# 2i.net
KiCad netlist of a schematic drawn in EAGLE
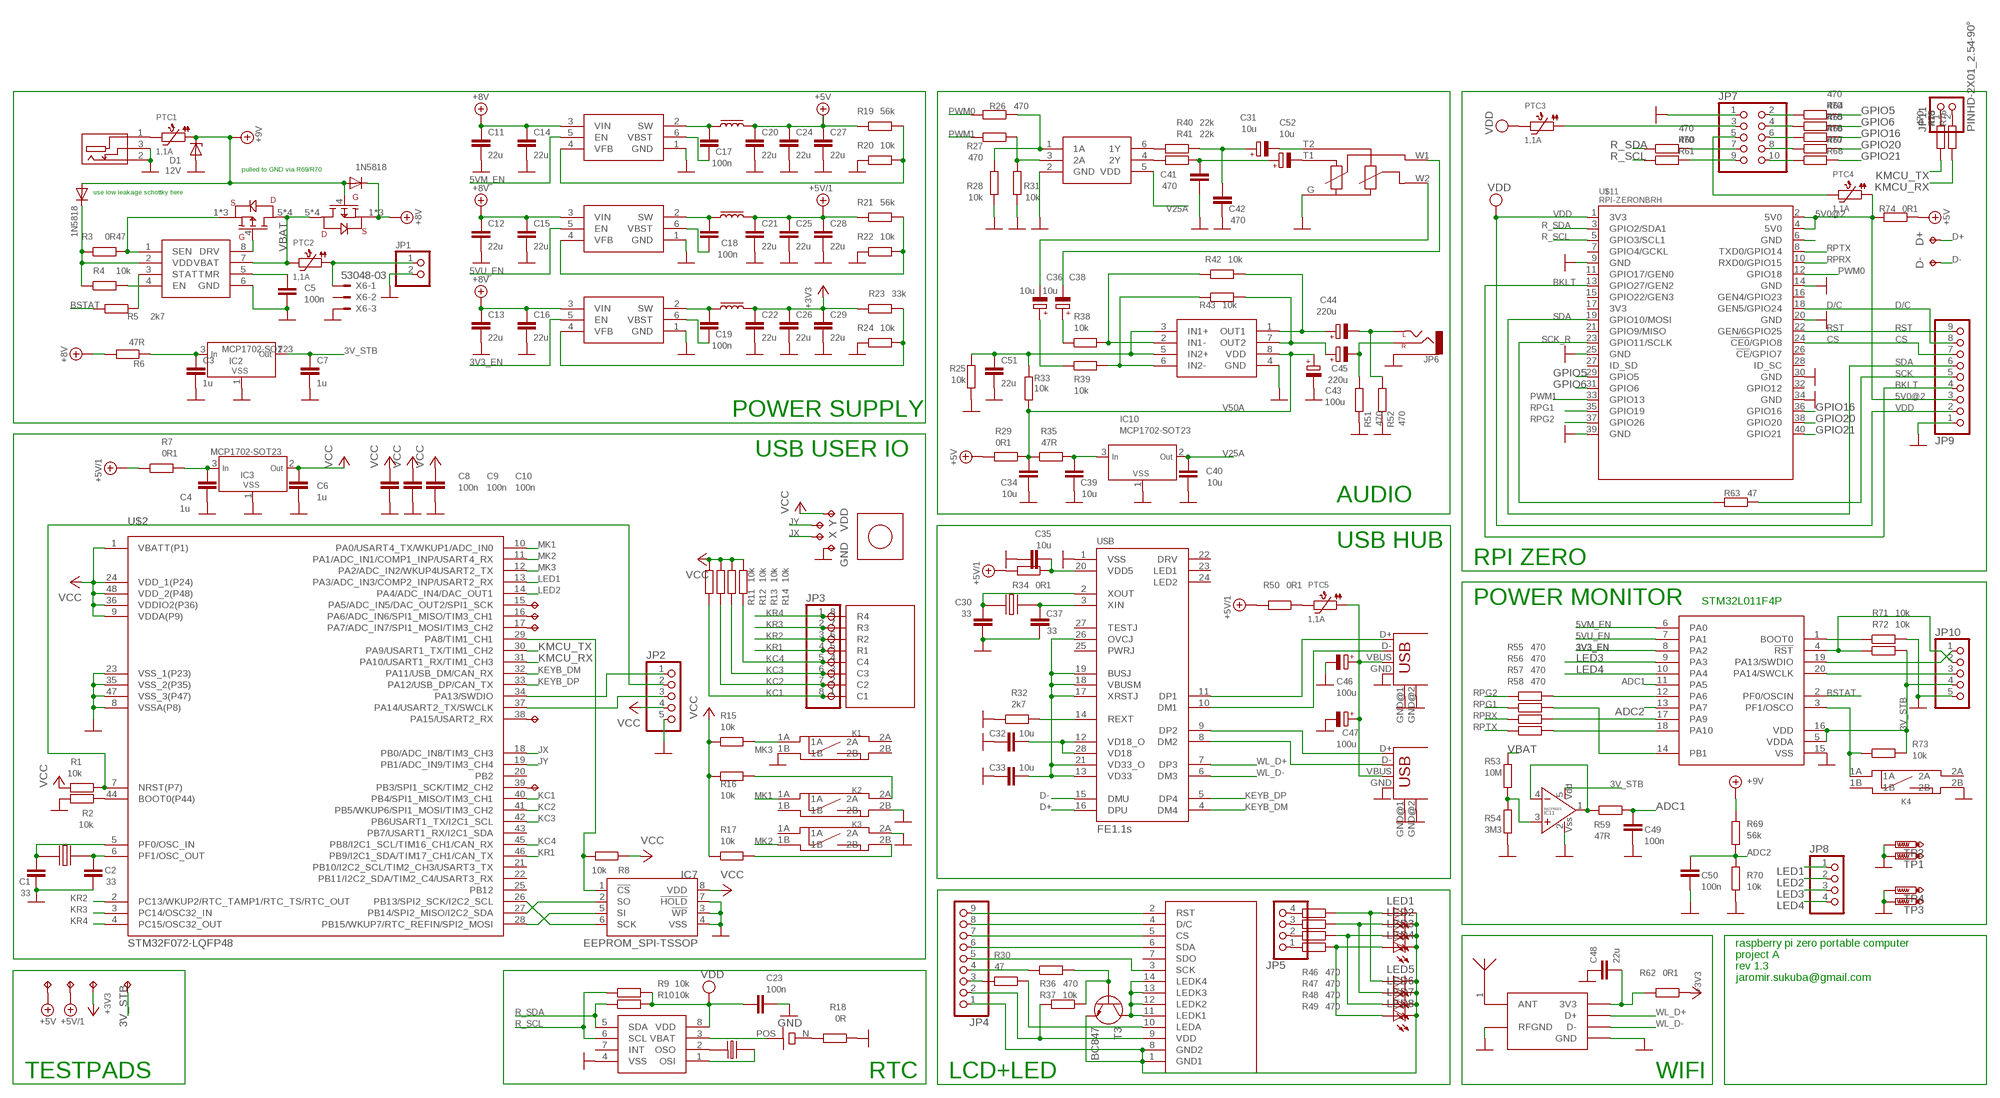
[diagram p0: schematic, sheet 1]

(export (version "E")
  (design (tool "Eeschema 10.0.6"))
  (components
    (comp (ref "ANT1")
      (value "ANT_RAINSUN_24GHZ")
      (footprint "eagle-import:ANT_RAINSUN-24G")
      (libsource (lib "eagle-import") (part "ANT_RAINSUN_24GHZ"))
    )
    (comp (ref "C1")
      (value "33")
      (footprint "eagle-import:R0805")
      (libsource (lib "eagle-import") (part "C_0806"))
    )
    (comp (ref "C2")
      (value "33")
      (footprint "eagle-import:R0805")
      (libsource (lib "eagle-import") (part "C_0806"))
    )
    (comp (ref "C3")
      (value "1u")
      (footprint "eagle-import:R0805")
      (libsource (lib "eagle-import") (part "C_0806"))
    )
    (comp (ref "C4")
      (value "1u")
      (footprint "eagle-import:R0805")
      (libsource (lib "eagle-import") (part "C_0806"))
    )
    (comp (ref "C5")
      (value "100n")
      (footprint "eagle-import:R0805")
      (libsource (lib "eagle-import") (part "C_0806"))
    )
    (comp (ref "C6")
      (value "1u")
      (footprint "eagle-import:R0805")
      (libsource (lib "eagle-import") (part "C_0806"))
    )
    (comp (ref "C7")
      (value "1u")
      (footprint "eagle-import:R0805")
      (libsource (lib "eagle-import") (part "C_0806"))
    )
    (comp (ref "C8")
      (value "100n")
      (footprint "eagle-import:R0805")
      (libsource (lib "eagle-import") (part "C_0806"))
    )
    (comp (ref "C9")
      (value "100n")
      (footprint "eagle-import:R0805")
      (libsource (lib "eagle-import") (part "C_0806"))
    )
    (comp (ref "C10")
      (value "100n")
      (footprint "eagle-import:R0805")
      (libsource (lib "eagle-import") (part "C_0806"))
    )
    (comp (ref "C11")
      (value "22u")
      (footprint "eagle-import:R0805")
      (libsource (lib "eagle-import") (part "C_0806"))
    )
    (comp (ref "C12")
      (value "22u")
      (footprint "eagle-import:R0805")
      (libsource (lib "eagle-import") (part "C_0806"))
    )
    (comp (ref "C13")
      (value "22u")
      (footprint "eagle-import:R0805")
      (libsource (lib "eagle-import") (part "C_0806"))
    )
    (comp (ref "C14")
      (value "22u")
      (footprint "eagle-import:R0805")
      (libsource (lib "eagle-import") (part "C_0806"))
    )
    (comp (ref "C15")
      (value "22u")
      (footprint "eagle-import:R0805")
      (libsource (lib "eagle-import") (part "C_0806"))
    )
    (comp (ref "C16")
      (value "22u")
      (footprint "eagle-import:R0805")
      (libsource (lib "eagle-import") (part "C_0806"))
    )
    (comp (ref "C17")
      (value "100n")
      (footprint "eagle-import:R0805")
      (libsource (lib "eagle-import") (part "C_0806"))
    )
    (comp (ref "C18")
      (value "100n")
      (footprint "eagle-import:R0805")
      (libsource (lib "eagle-import") (part "C_0806"))
    )
    (comp (ref "C19")
      (value "100n")
      (footprint "eagle-import:R0805")
      (libsource (lib "eagle-import") (part "C_0806"))
    )
    (comp (ref "C20")
      (value "22u")
      (footprint "eagle-import:R0805")
      (libsource (lib "eagle-import") (part "C_0806"))
    )
    (comp (ref "C21")
      (value "22u")
      (footprint "eagle-import:R0805")
      (libsource (lib "eagle-import") (part "C_0806"))
    )
    (comp (ref "C22")
      (value "22u")
      (footprint "eagle-import:R0805")
      (libsource (lib "eagle-import") (part "C_0806"))
    )
    (comp (ref "C23")
      (value "100n")
      (footprint "eagle-import:R0805")
      (libsource (lib "eagle-import") (part "C_0806"))
    )
    (comp (ref "C24")
      (value "22u")
      (footprint "eagle-import:R0805")
      (libsource (lib "eagle-import") (part "C_0806"))
    )
    (comp (ref "C25")
      (value "22u")
      (footprint "eagle-import:R0805")
      (libsource (lib "eagle-import") (part "C_0806"))
    )
    (comp (ref "C26")
      (value "22u")
      (footprint "eagle-import:R0805")
      (libsource (lib "eagle-import") (part "C_0806"))
    )
    (comp (ref "C27")
      (value "22u")
      (footprint "eagle-import:R0805")
      (libsource (lib "eagle-import") (part "C_0806"))
    )
    (comp (ref "C28")
      (value "22u")
      (footprint "eagle-import:R0805")
      (libsource (lib "eagle-import") (part "C_0806"))
    )
    (comp (ref "C29")
      (value "22u")
      (footprint "eagle-import:R0805")
      (libsource (lib "eagle-import") (part "C_0806"))
    )
    (comp (ref "C30")
      (value "33")
      (footprint "eagle-import:R0805")
      (libsource (lib "eagle-import") (part "C_0806"))
    )
    (comp (ref "C31")
      (value "10u")
      (footprint "eagle-import:PANASONIC_A")
      (libsource (lib "eagle-import") (part "CPOL-EUA"))
    )
    (comp (ref "C32")
      (value "10u")
      (footprint "eagle-import:R0805")
      (libsource (lib "eagle-import") (part "C_0806"))
    )
    (comp (ref "C33")
      (value "10u")
      (footprint "eagle-import:R0805")
      (libsource (lib "eagle-import") (part "C_0806"))
    )
    (comp (ref "C34")
      (value "10u")
      (footprint "eagle-import:R0805")
      (libsource (lib "eagle-import") (part "C_0806"))
    )
    (comp (ref "C35")
      (value "10u")
      (footprint "eagle-import:R0805")
      (libsource (lib "eagle-import") (part "C_0806"))
    )
    (comp (ref "C36")
      (value "10u")
      (footprint "eagle-import:PANASONIC_A")
      (libsource (lib "eagle-import") (part "CPOL-EUA"))
    )
    (comp (ref "C37")
      (value "33")
      (footprint "eagle-import:R0805")
      (libsource (lib "eagle-import") (part "C_0806"))
    )
    (comp (ref "C38")
      (value "10u")
      (footprint "eagle-import:PANASONIC_A")
      (libsource (lib "eagle-import") (part "CPOL-EUA"))
    )
    (comp (ref "C39")
      (value "10u")
      (footprint "eagle-import:R0805")
      (libsource (lib "eagle-import") (part "C_0806"))
    )
    (comp (ref "C40")
      (value "10u")
      (footprint "eagle-import:R0805")
      (libsource (lib "eagle-import") (part "C_0806"))
    )
    (comp (ref "C41")
      (value "470")
      (footprint "eagle-import:R0805")
      (libsource (lib "eagle-import") (part "C_0806"))
    )
    (comp (ref "C42")
      (value "470")
      (footprint "eagle-import:R0805")
      (libsource (lib "eagle-import") (part "C_0806"))
    )
    (comp (ref "C43")
      (value "100u")
      (footprint "eagle-import:PANASONIC_D")
      (libsource (lib "eagle-import") (part "CPOL-EUD"))
    )
    (comp (ref "C44")
      (value "220u")
      (footprint "eagle-import:PANASONIC_D")
      (libsource (lib "eagle-import") (part "CPOL-EUD"))
    )
    (comp (ref "C45")
      (value "220u")
      (footprint "eagle-import:PANASONIC_D")
      (libsource (lib "eagle-import") (part "CPOL-EUD"))
    )
    (comp (ref "C46")
      (value "100u")
      (footprint "eagle-import:PANASONIC_D")
      (libsource (lib "eagle-import") (part "CPOL-EUD"))
    )
    (comp (ref "C47")
      (value "100u")
      (footprint "eagle-import:PANASONIC_D")
      (libsource (lib "eagle-import") (part "CPOL-EUD"))
    )
    (comp (ref "C48")
      (value "22u")
      (footprint "eagle-import:R0805")
      (libsource (lib "eagle-import") (part "C_0806"))
    )
    (comp (ref "C49")
      (value "100n")
      (footprint "eagle-import:R0805")
      (libsource (lib "eagle-import") (part "C_0806"))
    )
    (comp (ref "C50")
      (value "100n")
      (footprint "eagle-import:R0805")
      (libsource (lib "eagle-import") (part "C_0806"))
    )
    (comp (ref "C51")
      (value "22u")
      (footprint "eagle-import:R0805")
      (libsource (lib "eagle-import") (part "C_0806"))
    )
    (comp (ref "C52")
      (value "10u")
      (footprint "eagle-import:PANASONIC_A")
      (libsource (lib "eagle-import") (part "CPOL-EUA"))
    )
    (comp (ref "D+")
      (value "TPTP14R")
      (footprint "eagle-import:TP14R")
      (libsource (lib "eagle-import") (part "TPTP14R"))
    )
    (comp (ref "D-")
      (value "TPTP14R")
      (footprint "eagle-import:TP14R")
      (libsource (lib "eagle-import") (part "TPTP14R"))
    )
    (comp (ref "D1")
      (value "12V")
      (footprint "eagle-import:SMB")
      (libsource (lib "eagle-import") (part "ZENER-DIODESMB"))
    )
    (comp (ref "D2")
      (value "1N5818")
      (footprint "eagle-import:SMB")
      (libsource (lib "eagle-import") (part "DIODE-SMB"))
    )
    (comp (ref "D3")
      (value "1N5818")
      (footprint "eagle-import:SMB")
      (libsource (lib "eagle-import") (part "DIODE-SMB"))
    )
    (comp (ref "GND")
      (value "TPTP14R")
      (footprint "eagle-import:TP14R")
      (libsource (lib "eagle-import") (part "TPTP14R"))
    )
    (comp (ref "IC1")
      (value "MCP73844")
      (footprint "eagle-import:MSOP8")
      (libsource (lib "eagle-import") (part "MCP73844"))
    )
    (comp (ref "IC2")
      (value "MCP1702-SOT23")
      (footprint "eagle-import:SOT23")
      (libsource (lib "eagle-import") (part "MCP1702-SOT23"))
    )
    (comp (ref "IC3")
      (value "MCP1702-SOT23")
      (footprint "eagle-import:SOT23")
      (libsource (lib "eagle-import") (part "MCP1702-SOT23"))
    )
    (comp (ref "IC4")
      (value "TPS562200")
      (footprint "eagle-import:SOT23-6")
      (libsource (lib "eagle-import") (part "TPS562200"))
    )
    (comp (ref "IC5")
      (value "TPS562200")
      (footprint "eagle-import:SOT23-6")
      (libsource (lib "eagle-import") (part "TPS562200"))
    )
    (comp (ref "IC6")
      (value "TPS562200")
      (footprint "eagle-import:SOT23-6")
      (libsource (lib "eagle-import") (part "TPS562200"))
    )
    (comp (ref "IC7")
      (value "EEPROM_SPI-TSSOP")
      (footprint "eagle-import:TSSOP8W")
      (libsource (lib "eagle-import") (part "EEPROM_SPI-TSSOP"))
    )
    (comp (ref "IC8")
      (value "PCF8523")
      (footprint "eagle-import:SO-08")
      (libsource (lib "eagle-import") (part "PCF8523"))
    )
    (comp (ref "IC9")
      (value "74LVC2G34")
      (footprint "eagle-import:SOT23-6")
      (libsource (lib "eagle-import") (part "74LVC2G34"))
    )
    (comp (ref "IC10")
      (value "MCP1702-SOT23")
      (footprint "eagle-import:SOT23")
      (libsource (lib "eagle-import") (part "MCP1702-SOT23"))
    )
    (comp (ref "IC11")
      (value "MCP6021")
      (footprint "eagle-import:SOT23-5L")
      (libsource (lib "eagle-import") (part "MCP6021"))
    )
    (comp (ref "JP1")
      (value "PINHD-1X02_2.54-90°")
      (footprint "eagle-import:1X02_90")
      (libsource (lib "eagle-import") (part "PINHD-1X02_2.54-90°"))
    )
    (comp (ref "JP2")
      (value "PINHD-1X05_2.54-90°")
      (footprint "eagle-import:1X05_90")
      (libsource (lib "eagle-import") (part "PINHD-1X05_2.54-90°"))
    )
    (comp (ref "JP3")
      (value "PINHD-1X08_2.54")
      (footprint "eagle-import:1X08")
      (libsource (lib "eagle-import") (part "PINHD-1X08_2.54"))
    )
    (comp (ref "JP4")
      (value "PINHD-1X09_2.00")
      (footprint "eagle-import:1X09M")
      (libsource (lib "eagle-import") (part "PINHD-1X09_2.00"))
    )
    (comp (ref "JP5")
      (value "PINHD-1X04_2.00")
      (footprint "eagle-import:1X04M")
      (libsource (lib "eagle-import") (part "PINHD-1X04_2.00"))
    )
    (comp (ref "JP6")
      (value "AUDIO-JACKPTH")
      (footprint "eagle-import:AUDIO-JACK")
      (libsource (lib "eagle-import") (part "AUDIO-JACKPTH"))
    )
    (comp (ref "JP7")
      (value "PINHD-2X05_2.54-90°")
      (footprint "eagle-import:2X05_90")
      (libsource (lib "eagle-import") (part "PINHD-2X05_2.54-90°"))
    )
    (comp (ref "JP8")
      (value "PINHD-1X04_2.00")
      (footprint "eagle-import:1X04M")
      (libsource (lib "eagle-import") (part "PINHD-1X04_2.00"))
    )
    (comp (ref "JP9")
      (value "PINHD-1X09_2.00")
      (footprint "eagle-import:1X09M")
      (libsource (lib "eagle-import") (part "PINHD-1X09_2.00"))
    )
    (comp (ref "JP10")
      (value "PINHD-1X05_2.54-90°")
      (footprint "eagle-import:1X05_90")
      (libsource (lib "eagle-import") (part "PINHD-1X05_2.54-90°"))
    )
    (comp (ref "JP11")
      (value "PINHD-2X01_2.54-90°")
      (footprint "eagle-import:2X01_90")
      (libsource (lib "eagle-import") (part "PINHD-2X01_2.54-90°"))
    )
    (comp (ref "K1")
      (value "SWITCH_BD_B")
      (footprint "eagle-import:SW_SMD2")
      (libsource (lib "eagle-import") (part "SWITCH_BD_B"))
    )
    (comp (ref "K2")
      (value "SWITCH_BD_B")
      (footprint "eagle-import:SW_SMD2")
      (libsource (lib "eagle-import") (part "SWITCH_BD_B"))
    )
    (comp (ref "K3")
      (value "SWITCH_BD_B")
      (footprint "eagle-import:SW_SMD2")
      (libsource (lib "eagle-import") (part "SWITCH_BD_B"))
    )
    (comp (ref "K4")
      (value "SWITCH_BD_B")
      (footprint "eagle-import:SW_SMD2")
      (libsource (lib "eagle-import") (part "SWITCH_BD_B"))
    )
    (comp (ref "LED1")
      (value "LED3MM")
      (footprint "eagle-import:LED3MM")
      (libsource (lib "eagle-import") (part "LED3MM"))
    )
    (comp (ref "LED2")
      (value "LED3MM")
      (footprint "eagle-import:LED3MM")
      (libsource (lib "eagle-import") (part "LED3MM"))
    )
    (comp (ref "LED3")
      (value "LED3MM")
      (footprint "eagle-import:LED3MM")
      (libsource (lib "eagle-import") (part "LED3MM"))
    )
    (comp (ref "LED4")
      (value "LED3MM")
      (footprint "eagle-import:LED3MM")
      (libsource (lib "eagle-import") (part "LED3MM"))
    )
    (comp (ref "LED5")
      (value "LEDCHIPLED_0805")
      (footprint "eagle-import:CHIPLED_0805")
      (libsource (lib "eagle-import") (part "LEDCHIPLED_0805"))
    )
    (comp (ref "LED6")
      (value "LEDCHIPLED_0805")
      (footprint "eagle-import:CHIPLED_0805")
      (libsource (lib "eagle-import") (part "LEDCHIPLED_0805"))
    )
    (comp (ref "LED7")
      (value "LEDCHIPLED_0805")
      (footprint "eagle-import:CHIPLED_0805")
      (libsource (lib "eagle-import") (part "LEDCHIPLED_0805"))
    )
    (comp (ref "LED8")
      (value "LEDCHIPLED_0805")
      (footprint "eagle-import:CHIPLED_0805")
      (libsource (lib "eagle-import") (part "LEDCHIPLED_0805"))
    )
    (comp (ref "MOD1")
      (value "MOD_USB_RTL8188")
      (footprint "eagle-import:MOD_USB_RTL8188")
      (libsource (lib "eagle-import") (part "MOD_USB_RTL8188"))
    )
    (comp (ref "PTC1")
      (value "1,1A")
      (footprint "eagle-import:PTC1812")
      (libsource (lib "eagle-import") (part "PTC1812"))
    )
    (comp (ref "PTC2")
      (value "1,1A")
      (footprint "eagle-import:PTC1812")
      (libsource (lib "eagle-import") (part "PTC1812"))
    )
    (comp (ref "PTC3")
      (value "1,1A")
      (footprint "eagle-import:PTC1812")
      (libsource (lib "eagle-import") (part "PTC1812"))
    )
    (comp (ref "PTC4")
      (value "1,1A")
      (footprint "eagle-import:PTC1812")
      (libsource (lib "eagle-import") (part "PTC1812"))
    )
    (comp (ref "PTC5")
      (value "1,1A")
      (footprint "eagle-import:PTC1812")
      (libsource (lib "eagle-import") (part "PTC1812"))
    )
    (comp (ref "Q1")
      (value "CRYSTAL87X38")
      (footprint "eagle-import:CRYST_32K_87X38MM")
      (libsource (lib "eagle-import") (part "CRYSTAL87X38"))
    )
    (comp (ref "R1")
      (value "10k")
      (footprint "eagle-import:R0805")
      (libsource (lib "eagle-import") (part "R_0805"))
    )
    (comp (ref "R2")
      (value "10k")
      (footprint "eagle-import:R0805")
      (libsource (lib "eagle-import") (part "R_0805"))
    )
    (comp (ref "R3")
      (value "0R47")
      (footprint "eagle-import:R1206")
      (libsource (lib "eagle-import") (part "R_1206"))
    )
    (comp (ref "R4")
      (value "10k")
      (footprint "eagle-import:R0805")
      (libsource (lib "eagle-import") (part "R_0805"))
    )
    (comp (ref "R5")
      (value "2k7")
      (footprint "eagle-import:R0805")
      (libsource (lib "eagle-import") (part "R_0805"))
    )
    (comp (ref "R6")
      (value "47R")
      (footprint "eagle-import:R0805")
      (libsource (lib "eagle-import") (part "R_0805"))
    )
    (comp (ref "R7")
      (value "0R1")
      (footprint "eagle-import:R1206")
      (libsource (lib "eagle-import") (part "R_1206"))
    )
    (comp (ref "R8")
      (value "10k")
      (footprint "eagle-import:R0805")
      (libsource (lib "eagle-import") (part "R_0805"))
    )
    (comp (ref "R9")
      (value "10k")
      (footprint "eagle-import:R0805")
      (libsource (lib "eagle-import") (part "R_0805"))
    )
    (comp (ref "R10")
      (value "10k")
      (footprint "eagle-import:R0805")
      (libsource (lib "eagle-import") (part "R_0805"))
    )
    (comp (ref "R11")
      (value "10k")
      (footprint "eagle-import:R0805")
      (libsource (lib "eagle-import") (part "R_0805"))
    )
    (comp (ref "R12")
      (value "10k")
      (footprint "eagle-import:R0805")
      (libsource (lib "eagle-import") (part "R_0805"))
    )
    (comp (ref "R13")
      (value "10k")
      (footprint "eagle-import:R0805")
      (libsource (lib "eagle-import") (part "R_0805"))
    )
    (comp (ref "R14")
      (value "10k")
      (footprint "eagle-import:R0805")
      (libsource (lib "eagle-import") (part "R_0805"))
    )
    (comp (ref "R15")
      (value "10k")
      (footprint "eagle-import:R0805")
      (libsource (lib "eagle-import") (part "R_0805"))
    )
    (comp (ref "R16")
      (value "10k")
      (footprint "eagle-import:R0805")
      (libsource (lib "eagle-import") (part "R_0805"))
    )
    (comp (ref "R17")
      (value "10k")
      (footprint "eagle-import:R0805")
      (libsource (lib "eagle-import") (part "R_0805"))
    )
    (comp (ref "R18")
      (value "0R")
      (footprint "eagle-import:R0805")
      (libsource (lib "eagle-import") (part "R_0805"))
    )
    (comp (ref "R19")
      (value "56k")
      (footprint "eagle-import:R0805")
      (libsource (lib "eagle-import") (part "R_0805"))
    )
    (comp (ref "R20")
      (value "10k")
      (footprint "eagle-import:R0805")
      (libsource (lib "eagle-import") (part "R_0805"))
    )
    (comp (ref "R21")
      (value "56k")
      (footprint "eagle-import:R0805")
      (libsource (lib "eagle-import") (part "R_0805"))
    )
    (comp (ref "R22")
      (value "10k")
      (footprint "eagle-import:R0805")
      (libsource (lib "eagle-import") (part "R_0805"))
    )
    (comp (ref "R23")
      (value "33k")
      (footprint "eagle-import:R0805")
      (libsource (lib "eagle-import") (part "R_0805"))
    )
    (comp (ref "R24")
      (value "10k")
      (footprint "eagle-import:R0805")
      (libsource (lib "eagle-import") (part "R_0805"))
    )
    (comp (ref "R25")
      (value "10k")
      (footprint "eagle-import:R0805")
      (libsource (lib "eagle-import") (part "R_0805"))
    )
    (comp (ref "R26")
      (value "470")
      (footprint "eagle-import:R0805")
      (libsource (lib "eagle-import") (part "R_0805"))
    )
    (comp (ref "R27")
      (value "470")
      (footprint "eagle-import:R0805")
      (libsource (lib "eagle-import") (part "R_0805"))
    )
    (comp (ref "R28")
      (value "10k")
      (footprint "eagle-import:R0805")
      (libsource (lib "eagle-import") (part "R_0805"))
    )
    (comp (ref "R29")
      (value "0R1")
      (footprint "eagle-import:R1206")
      (libsource (lib "eagle-import") (part "R_1206"))
    )
    (comp (ref "R30")
      (value "47")
      (footprint "eagle-import:R0805")
      (libsource (lib "eagle-import") (part "R_0805"))
    )
    (comp (ref "R31")
      (value "10k")
      (footprint "eagle-import:R0805")
      (libsource (lib "eagle-import") (part "R_0805"))
    )
    (comp (ref "R32")
      (value "2k7")
      (footprint "eagle-import:R0805")
      (libsource (lib "eagle-import") (part "R_0805"))
    )
    (comp (ref "R33")
      (value "10k")
      (footprint "eagle-import:R0805")
      (libsource (lib "eagle-import") (part "R_0805"))
    )
    (comp (ref "R34")
      (value "0R1")
      (footprint "eagle-import:R1206")
      (libsource (lib "eagle-import") (part "R_1206"))
    )
    (comp (ref "R35")
      (value "47R")
      (footprint "eagle-import:R0805")
      (libsource (lib "eagle-import") (part "R_0805"))
    )
    (comp (ref "R36")
      (value "470")
      (footprint "eagle-import:R0805")
      (libsource (lib "eagle-import") (part "R_0805"))
    )
    (comp (ref "R37")
      (value "10k")
      (footprint "eagle-import:R0805")
      (libsource (lib "eagle-import") (part "R_0805"))
    )
    (comp (ref "R38")
      (value "10k")
      (footprint "eagle-import:R0805")
      (libsource (lib "eagle-import") (part "R_0805"))
    )
    (comp (ref "R39")
      (value "10k")
      (footprint "eagle-import:R0805")
      (libsource (lib "eagle-import") (part "R_0805"))
    )
    (comp (ref "R40")
      (value "22k")
      (footprint "eagle-import:R0805")
      (libsource (lib "eagle-import") (part "R_0805"))
    )
    (comp (ref "R41")
      (value "22k")
      (footprint "eagle-import:R0805")
      (libsource (lib "eagle-import") (part "R_0805"))
    )
    (comp (ref "R42")
      (value "10k")
      (footprint "eagle-import:R0805")
      (libsource (lib "eagle-import") (part "R_0805"))
    )
    (comp (ref "R43")
      (value "10k")
      (footprint "eagle-import:R0805")
      (libsource (lib "eagle-import") (part "R_0805"))
    )
    (comp (ref "R46")
      (value "470")
      (footprint "eagle-import:R0805")
      (libsource (lib "eagle-import") (part "R_0805"))
    )
    (comp (ref "R47")
      (value "470")
      (footprint "eagle-import:R0805")
      (libsource (lib "eagle-import") (part "R_0805"))
    )
    (comp (ref "R48")
      (value "470")
      (footprint "eagle-import:R0805")
      (libsource (lib "eagle-import") (part "R_0805"))
    )
    (comp (ref "R49")
      (value "470")
      (footprint "eagle-import:R0805")
      (libsource (lib "eagle-import") (part "R_0805"))
    )
    (comp (ref "R50")
      (value "0R1")
      (footprint "eagle-import:R1206")
      (libsource (lib "eagle-import") (part "R_1206"))
    )
    (comp (ref "R51")
      (value "470")
      (footprint "eagle-import:R0805")
      (libsource (lib "eagle-import") (part "R_0805"))
    )
    (comp (ref "R52")
      (value "470")
      (footprint "eagle-import:R0805")
      (libsource (lib "eagle-import") (part "R_0805"))
    )
    (comp (ref "R53")
      (value "10M")
      (footprint "eagle-import:R0805")
      (libsource (lib "eagle-import") (part "R_0805"))
    )
    (comp (ref "R54")
      (value "3M3")
      (footprint "eagle-import:R0805")
      (libsource (lib "eagle-import") (part "R_0805"))
    )
    (comp (ref "R55")
      (value "470")
      (footprint "eagle-import:R0805")
      (libsource (lib "eagle-import") (part "R_0805"))
    )
    (comp (ref "R56")
      (value "470")
      (footprint "eagle-import:R0805")
      (libsource (lib "eagle-import") (part "R_0805"))
    )
    (comp (ref "R57")
      (value "470")
      (footprint "eagle-import:R0805")
      (libsource (lib "eagle-import") (part "R_0805"))
    )
    (comp (ref "R58")
      (value "470")
      (footprint "eagle-import:R0805")
      (libsource (lib "eagle-import") (part "R_0805"))
    )
    (comp (ref "R59")
      (value "47R")
      (footprint "eagle-import:R0805")
      (libsource (lib "eagle-import") (part "R_0805"))
    )
    (comp (ref "R60")
      (value "470")
      (footprint "eagle-import:R0805")
      (libsource (lib "eagle-import") (part "R_0805"))
    )
    (comp (ref "R61")
      (value "470")
      (footprint "eagle-import:R0805")
      (libsource (lib "eagle-import") (part "R_0805"))
    )
    (comp (ref "R62")
      (value "0R1")
      (footprint "eagle-import:R1206")
      (libsource (lib "eagle-import") (part "R_1206"))
    )
    (comp (ref "R63")
      (value "47")
      (footprint "eagle-import:R0805")
      (libsource (lib "eagle-import") (part "R_0805"))
    )
    (comp (ref "R64")
      (value "470")
      (footprint "eagle-import:R0805")
      (libsource (lib "eagle-import") (part "R_0805"))
    )
    (comp (ref "R65")
      (value "470")
      (footprint "eagle-import:R0805")
      (libsource (lib "eagle-import") (part "R_0805"))
    )
    (comp (ref "R66")
      (value "470")
      (footprint "eagle-import:R0805")
      (libsource (lib "eagle-import") (part "R_0805"))
    )
    (comp (ref "R67")
      (value "470")
      (footprint "eagle-import:R0805")
      (libsource (lib "eagle-import") (part "R_0805"))
    )
    (comp (ref "R68")
      (value "470")
      (footprint "eagle-import:R0805")
      (libsource (lib "eagle-import") (part "R_0805"))
    )
    (comp (ref "R69")
      (value "56k")
      (footprint "eagle-import:R0805")
      (libsource (lib "eagle-import") (part "R_0805"))
    )
    (comp (ref "R70")
      (value "10k")
      (footprint "eagle-import:R0805")
      (libsource (lib "eagle-import") (part "R_0805"))
    )
    (comp (ref "R71")
      (value "10k")
      (footprint "eagle-import:R0805")
      (libsource (lib "eagle-import") (part "R_0805"))
    )
    (comp (ref "R72")
      (value "10k")
      (footprint "eagle-import:R0805")
      (libsource (lib "eagle-import") (part "R_0805"))
    )
    (comp (ref "R73")
      (value "10k")
      (footprint "eagle-import:R0805")
      (libsource (lib "eagle-import") (part "R_0805"))
    )
    (comp (ref "R74")
      (value "0R1")
      (footprint "eagle-import:R1206")
      (libsource (lib "eagle-import") (part "R_1206"))
    )
    (comp (ref "R75")
      (value "470")
      (footprint "eagle-import:R0805")
      (libsource (lib "eagle-import") (part "R_0805"))
    )
    (comp (ref "R76")
      (value "470")
      (footprint "eagle-import:R0805")
      (libsource (lib "eagle-import") (part "R_0805"))
    )
    (comp (ref "T1")
      (value "PFET_SO8")
      (footprint "eagle-import:SO-08")
      (libsource (lib "eagle-import") (part "PFET_SO8"))
    )
    (comp (ref "T2")
      (value "PFET_SO8")
      (footprint "eagle-import:SO-08")
      (libsource (lib "eagle-import") (part "PFET_SO8"))
    )
    (comp (ref "T3")
      (value "BC847")
      (footprint "eagle-import:SOT23")
      (libsource (lib "eagle-import") (part "BC847"))
    )
    (comp (ref "TFT1")
      (value "DISP_ILI_28")
      (footprint "eagle-import:DISP_ILI_28")
      (libsource (lib "eagle-import") (part "DISP_ILI_28"))
    )
    (comp (ref "TP1")
      (value "PTR1PAD1-13")
      (footprint "eagle-import:P1-13")
      (libsource (lib "eagle-import") (part "PTR1PAD1-13"))
    )
    (comp (ref "TP2")
      (value "PTR1PAD1-13")
      (footprint "eagle-import:P1-13")
      (libsource (lib "eagle-import") (part "PTR1PAD1-13"))
    )
    (comp (ref "TP3")
      (value "PTR1PAD1-13")
      (footprint "eagle-import:P1-13")
      (libsource (lib "eagle-import") (part "PTR1PAD1-13"))
    )
    (comp (ref "TP4")
      (value "PTR1PAD1-13")
      (footprint "eagle-import:P1-13")
      (libsource (lib "eagle-import") (part "PTR1PAD1-13"))
    )
    (comp (ref "U$1")
      (value "CONN_DC_13")
      (footprint "eagle-import:CON_DC13")
      (libsource (lib "eagle-import") (part "CONN_DC_13"))
    )
    (comp (ref "U$2")
      (value "STM32F072-LQFP48")
      (footprint "eagle-import:LQFP48")
      (libsource (lib "eagle-import") (part "STM32F072-LQFP48"))
    )
    (comp (ref "U$3")
      (value "2u2")
      (footprint "eagle-import:BOURNS_SRP7030")
      (libsource (lib "eagle-import") (part "INDUCTORBOURNS_SRP7030"))
    )
    (comp (ref "U$4")
      (value "2u2")
      (footprint "eagle-import:BOURNS_SRP7030")
      (libsource (lib "eagle-import") (part "INDUCTORBOURNS_SRP7030"))
    )
    (comp (ref "U$5")
      (value "2u2")
      (footprint "eagle-import:BOURNS_SRP7030")
      (libsource (lib "eagle-import") (part "INDUCTORBOURNS_SRP7030"))
    )
    (comp (ref "U$6")
      (value "BATTH1220")
      (footprint "eagle-import:BATT_HOLDER_DS1092-12")
      (libsource (lib "eagle-import") (part "BATTH1220"))
    )
    (comp (ref "U$7")
      (value "KB1604")
      (footprint "eagle-import:KB1604")
      (libsource (lib "eagle-import") (part "KB1604"))
    )
    (comp (ref "U$8")
      (value "JOY_PS")
      (footprint "eagle-import:JOY_PS")
      (libsource (lib "eagle-import") (part "JOY_PS"))
    )
    (comp (ref "U$9")
      (value "TDA1308")
      (footprint "eagle-import:SO-08")
      (libsource (lib "eagle-import") (part "TDA1308"))
    )
    (comp (ref "U$10")
      (value "POT_DUAL_14X2")
      (footprint "eagle-import:POT_14X2DUAL")
      (libsource (lib "eagle-import") (part "POT_DUAL_14X2"))
    )
    (comp (ref "U$11")
      (value "RPI-ZERONBRH")
      (footprint "eagle-import:RPI_ZERO_NBRH")
      (libsource (lib "eagle-import") (part "RPI-ZERONBRH"))
    )
    (comp (ref "U$12")
      (value "STM32F030_20")
      (footprint "eagle-import:TSSOP20")
      (libsource (lib "eagle-import") (part "STM32F030_20"))
    )
    (comp (ref "USB")
      (value "FE1.1S")
      (footprint "eagle-import:FE1.1S_SSOP-28")
      (libsource (lib "eagle-import") (part "FE1.1S"))
    )
    (comp (ref "USB1")
      (value "USB-A-S")
      (footprint "eagle-import:USB-A-S")
      (libsource (lib "eagle-import") (part "USB-A-S"))
    )
    (comp (ref "USB2")
      (value "USB-A-S")
      (footprint "eagle-import:USB-A-S")
      (libsource (lib "eagle-import") (part "USB-A-S"))
    )
    (comp (ref "VDD")
      (value "TPTP14R")
      (footprint "eagle-import:TP14R")
      (libsource (lib "eagle-import") (part "TPTP14R"))
    )
    (comp (ref "X")
      (value "TPTP14R")
      (footprint "eagle-import:TP14R")
      (libsource (lib "eagle-import") (part "TPTP14R"))
    )
    (comp (ref "X1")
      (value "TPTP14R")
      (footprint "eagle-import:TP14R")
      (libsource (lib "eagle-import") (part "TPTP14R"))
    )
    (comp (ref "X2")
      (value "CRYST_TC26SMXAS")
      (footprint "eagle-import:CR_12SMXA_S")
      (libsource (lib "eagle-import") (part "CRYST_TC26SMXAS"))
    )
    (comp (ref "X3")
      (value "TPTP14R")
      (footprint "eagle-import:TP14R")
      (libsource (lib "eagle-import") (part "TPTP14R"))
    )
    (comp (ref "X4")
      (value "TPTP14R")
      (footprint "eagle-import:TP14R")
      (libsource (lib "eagle-import") (part "TPTP14R"))
    )
    (comp (ref "X5")
      (value "TPTP14R")
      (footprint "eagle-import:TP14R")
      (libsource (lib "eagle-import") (part "TPTP14R"))
    )
    (comp (ref "X6")
      (value "53048-03")
      (footprint "eagle-import:53048-03")
      (fields (field (name "MF") "WALDOM/MOLEX") (field (name "MPN") "53048-0310"))
      (libsource (lib "eagle-import") (part "53?-03048"))
    )
    (comp (ref "X7")
      (value "TPTP14R")
      (footprint "eagle-import:TP14R")
      (libsource (lib "eagle-import") (part "TPTP14R"))
    )
    (comp (ref "X8")
      (value "TPTP14R")
      (footprint "eagle-import:TP14R")
      (libsource (lib "eagle-import") (part "TPTP14R"))
    )
    (comp (ref "X9")
      (value "TPTP14R")
      (footprint "eagle-import:TP14R")
      (libsource (lib "eagle-import") (part "TPTP14R"))
    )
    (comp (ref "X12")
      (value "TPTP14R")
      (footprint "eagle-import:TP14R")
      (libsource (lib "eagle-import") (part "TPTP14R"))
    )
    (comp (ref "X13")
      (value "TPTP14R")
      (footprint "eagle-import:TP14R")
      (libsource (lib "eagle-import") (part "TPTP14R"))
    )
    (comp (ref "X14")
      (value "CRYST_TC26SMXAS")
      (footprint "eagle-import:CR_12SMXA_S")
      (libsource (lib "eagle-import") (part "CRYST_TC26SMXAS"))
    )
    (comp (ref "Y")
      (value "TPTP14R")
      (footprint "eagle-import:TP14R")
      (libsource (lib "eagle-import") (part "TPTP14R"))
    )
  )
  (nets
    (net (code "1") (name "+3V3") (class "Default")
      (node (ref "C22") (pin "1") (pinfunction "1_1") (pintype "passive"))
      (node (ref "C26") (pin "1") (pinfunction "1_1") (pintype "passive"))
      (node (ref "C29") (pin "1") (pinfunction "1_1") (pintype "passive"))
      (node (ref "R23") (pin "1") (pinfunction "1_1") (pintype "passive"))
      (node (ref "R62") (pin "1") (pinfunction "1_1") (pintype "passive"))
      (node (ref "U$5") (pin "P$2") (pinfunction "P$2_P$2") (pintype "bidirectional"))
      (node (ref "X4") (pin "TP") (pinfunction "TP_TP") (pintype "input"))
    )
    (net (code "2") (name "+5V") (class "Default")
      (node (ref "C20") (pin "1") (pinfunction "1_1") (pintype "passive"))
      (node (ref "C24") (pin "1") (pinfunction "1_1") (pintype "passive"))
      (node (ref "C27") (pin "1") (pinfunction "1_1") (pintype "passive"))
      (node (ref "R19") (pin "1") (pinfunction "1_1") (pintype "passive"))
      (node (ref "R29") (pin "2") (pinfunction "2_2") (pintype "passive"))
      (node (ref "R74") (pin "1") (pinfunction "1_1") (pintype "passive"))
      (node (ref "U$3") (pin "P$2") (pinfunction "P$2_P$2") (pintype "bidirectional"))
      (node (ref "X1") (pin "TP") (pinfunction "TP_TP") (pintype "input"))
    )
    (net (code "3") (name "+5V{slash}1") (class "Default")
      (node (ref "C21") (pin "1") (pinfunction "1_1") (pintype "passive"))
      (node (ref "C25") (pin "1") (pinfunction "1_1") (pintype "passive"))
      (node (ref "C28") (pin "1") (pinfunction "1_1") (pintype "passive"))
      (node (ref "R21") (pin "1") (pinfunction "1_1") (pintype "passive"))
      (node (ref "R34") (pin "2") (pinfunction "2_2") (pintype "passive"))
      (node (ref "R50") (pin "2") (pinfunction "2_2") (pintype "passive"))
      (node (ref "R7") (pin "1") (pinfunction "1_1") (pintype "passive"))
      (node (ref "U$4") (pin "P$2") (pinfunction "P$2_P$2") (pintype "bidirectional"))
      (node (ref "X3") (pin "TP") (pinfunction "TP_TP") (pintype "input"))
    )
    (net (code "4") (name "+8V") (class "Default")
      (node (ref "C11") (pin "1") (pinfunction "1_1") (pintype "passive"))
      (node (ref "C12") (pin "1") (pinfunction "1_1") (pintype "passive"))
      (node (ref "C13") (pin "1") (pinfunction "1_1") (pintype "passive"))
      (node (ref "C14") (pin "1") (pinfunction "1_1") (pintype "passive"))
      (node (ref "C15") (pin "1") (pinfunction "1_1") (pintype "passive"))
      (node (ref "C16") (pin "1") (pinfunction "1_1") (pintype "passive"))
      (node (ref "D3") (pin "C") (pinfunction "C_C") (pintype "passive"))
      (node (ref "IC4") (pin "3") (pinfunction "VIN_3") (pintype "bidirectional"))
      (node (ref "IC5") (pin "3") (pinfunction "VIN_3") (pintype "bidirectional"))
      (node (ref "IC6") (pin "3") (pinfunction "VIN_3") (pintype "bidirectional"))
      (node (ref "R6") (pin "2") (pinfunction "2_2") (pintype "passive"))
      (node (ref "T2") (pin "1") (pinfunction "S_1") (pintype "bidirectional"))
      (node (ref "T2") (pin "2") (pinfunction "S_2") (pintype "bidirectional"))
      (node (ref "T2") (pin "3") (pinfunction "S_3") (pintype "bidirectional"))
    )
    (net (code "5") (name "+9V") (class "Default")
      (node (ref "D1") (pin "C") (pinfunction "C_C") (pintype "passive"))
      (node (ref "D2") (pin "A") (pinfunction "A_A") (pintype "passive"))
      (node (ref "D3") (pin "A") (pinfunction "A_A") (pintype "passive"))
      (node (ref "PTC1") (pin "P$1") (pinfunction "1_P$1") (pintype "passive"))
      (node (ref "R69") (pin "2") (pinfunction "2_2") (pintype "passive"))
      (node (ref "T2") (pin "4") (pinfunction "G_4") (pintype "bidirectional"))
    )
    (net (code "6") (name "/3V3") (class "Default")
      (node (ref "U$11") (pin "17") (pinfunction "3V3_17") (pintype "power_in"))
    )
    (net (code "7") (name "/3V3_EN") (class "Default")
      (node (ref "IC6") (pin "5") (pinfunction "EN_5") (pintype "bidirectional"))
      (node (ref "U$12") (pin "8") (pinfunction "PA2_8") (pintype "bidirectional"))
    )
    (net (code "8") (name "/3V_STB") (class "Default")
      (node (ref "C7") (pin "1") (pinfunction "1_1") (pintype "passive"))
      (node (ref "IC11") (pin "5") (pinfunction "VDD_5") (pintype "power_in"))
      (node (ref "IC2") (pin "2") (pinfunction "OUT_2") (pintype "output"))
      (node (ref "JP10") (pin "4") (pinfunction "4_4") (pintype "passive"))
      (node (ref "R72") (pin "2") (pinfunction "2_2") (pintype "passive"))
      (node (ref "R73") (pin "2") (pinfunction "2_2") (pintype "passive"))
      (node (ref "U$12") (pin "16") (pinfunction "VDD_16") (pintype "bidirectional"))
      (node (ref "U$12") (pin "5") (pinfunction "VDDA_5") (pintype "bidirectional"))
      (node (ref "X5") (pin "TP") (pinfunction "TP_TP") (pintype "input"))
    )
    (net (code "9") (name "/5V0@2") (class "Default")
      (node (ref "JP9") (pin "3") (pinfunction "3_3") (pintype "passive"))
      (node (ref "PTC4") (pin "P$1") (pinfunction "1_P$1") (pintype "passive"))
      (node (ref "R74") (pin "2") (pinfunction "2_2") (pintype "passive"))
      (node (ref "U$11") (pin "2") (pinfunction "5V0_2") (pintype "power_in"))
      (node (ref "U$11") (pin "4") (pinfunction "5V0_4") (pintype "power_in"))
    )
    (net (code "10") (name "/5VM_EN") (class "Default")
      (node (ref "IC4") (pin "5") (pinfunction "EN_5") (pintype "bidirectional"))
      (node (ref "U$12") (pin "6") (pinfunction "PA0_6") (pintype "bidirectional"))
    )
    (net (code "11") (name "/5VU_EN") (class "Default")
      (node (ref "IC5") (pin "5") (pinfunction "EN_5") (pintype "bidirectional"))
      (node (ref "U$12") (pin "7") (pinfunction "PA1_7") (pintype "bidirectional"))
    )
    (net (code "12") (name "/ADC1") (class "Default")
      (node (ref "C49") (pin "2") (pinfunction "2_2") (pintype "passive"))
      (node (ref "R59") (pin "1") (pinfunction "1_1") (pintype "passive"))
      (node (ref "U$12") (pin "11") (pinfunction "PA5_11") (pintype "bidirectional"))
    )
    (net (code "13") (name "/ADC2") (class "Default")
      (node (ref "C50") (pin "2") (pinfunction "2_2") (pintype "passive"))
      (node (ref "R69") (pin "1") (pinfunction "1_1") (pintype "passive"))
      (node (ref "R70") (pin "2") (pinfunction "2_2") (pintype "passive"))
      (node (ref "U$12") (pin "13") (pinfunction "PA7_13") (pintype "bidirectional"))
    )
    (net (code "14") (name "/BKLT") (class "Default")
      (node (ref "JP9") (pin "4") (pinfunction "4_4") (pintype "passive"))
      (node (ref "U$11") (pin "13") (pinfunction "GPIO27/GEN2_13") (pintype "bidirectional"))
    )
    (net (code "15") (name "/BSTAT") (class "Default")
      (node (ref "R5") (pin "2") (pinfunction "2_2") (pintype "passive"))
      (node (ref "U$12") (pin "2") (pinfunction "PF0/OSCIN_2") (pintype "bidirectional"))
    )
    (net (code "16") (name "/CS") (class "Default")
      (node (ref "JP9") (pin "7") (pinfunction "7_7") (pintype "passive"))
      (node (ref "U$11") (pin "24") (pinfunction "~{CE0}/GPIO8_24") (pintype "bidirectional"))
    )
    (net (code "17") (name "/D+") (class "Default")
      (node (ref "D+") (pin "TP") (pinfunction "TP_TP") (pintype "input"))
      (node (ref "USB") (pin "16") (pinfunction "DPU_16") (pintype "bidirectional"))
    )
    (net (code "18") (name "/D-") (class "Default")
      (node (ref "D-") (pin "TP") (pinfunction "TP_TP") (pintype "input"))
      (node (ref "USB") (pin "15") (pinfunction "DMU_15") (pintype "bidirectional"))
    )
    (net (code "19") (name "/D{slash}C") (class "Default")
      (node (ref "JP9") (pin "8") (pinfunction "8_8") (pintype "passive"))
      (node (ref "U$11") (pin "18") (pinfunction "GEN5/GPIO24_18") (pintype "bidirectional"))
    )
    (net (code "20") (name "/GPIO5") (class "Default")
      (node (ref "R64") (pin "2") (pinfunction "2_2") (pintype "passive"))
      (node (ref "U$11") (pin "29") (pinfunction "GPIO5_29") (pintype "bidirectional"))
    )
    (net (code "21") (name "/GPIO6") (class "Default")
      (node (ref "R65") (pin "2") (pinfunction "2_2") (pintype "passive"))
      (node (ref "U$11") (pin "31") (pinfunction "GPIO6_31") (pintype "bidirectional"))
    )
    (net (code "22") (name "/GPIO16") (class "Default")
      (node (ref "R66") (pin "2") (pinfunction "2_2") (pintype "passive"))
      (node (ref "U$11") (pin "36") (pinfunction "GPIO16_36") (pintype "bidirectional"))
    )
    (net (code "23") (name "/GPIO20") (class "Default")
      (node (ref "R67") (pin "2") (pinfunction "2_2") (pintype "passive"))
      (node (ref "U$11") (pin "38") (pinfunction "GPIO20_38") (pintype "bidirectional"))
    )
    (net (code "24") (name "/GPIO21") (class "Default")
      (node (ref "R68") (pin "2") (pinfunction "2_2") (pintype "passive"))
      (node (ref "U$11") (pin "40") (pinfunction "GPIO21_40") (pintype "bidirectional"))
    )
    (net (code "25") (name "/JX") (class "Default")
      (node (ref "U$2") (pin "18") (pinfunction "PB0/ADC_IN8/TIM3_CH3_18") (pintype "bidirectional"))
      (node (ref "X") (pin "TP") (pinfunction "TP_TP") (pintype "input"))
    )
    (net (code "26") (name "/JY") (class "Default")
      (node (ref "U$2") (pin "19") (pinfunction "PB1/ADC_IN9/TIM3_CH4_19") (pintype "bidirectional"))
      (node (ref "Y") (pin "TP") (pinfunction "TP_TP") (pintype "input"))
    )
    (net (code "27") (name "/KC1") (class "Default")
      (node (ref "JP3") (pin "8") (pinfunction "8_8") (pintype "passive"))
      (node (ref "R11") (pin "1") (pinfunction "1_1") (pintype "passive"))
      (node (ref "U$2") (pin "40") (pinfunction "PB4/SPI1_MISO/TIM3_CH1_40") (pintype "bidirectional"))
      (node (ref "U$7") (pin "1") (pinfunction "C1_1") (pintype "bidirectional"))
    )
    (net (code "28") (name "/KC2") (class "Default")
      (node (ref "JP3") (pin "7") (pinfunction "7_7") (pintype "passive"))
      (node (ref "R12") (pin "1") (pinfunction "1_1") (pintype "passive"))
      (node (ref "U$2") (pin "41") (pinfunction "PB5/WKUP6/SPI1_MOSI/TIM3_CH2_41") (pintype "bidirectional"))
      (node (ref "U$7") (pin "2") (pinfunction "C2_2") (pintype "bidirectional"))
    )
    (net (code "29") (name "/KC3") (class "Default")
      (node (ref "JP3") (pin "6") (pinfunction "6_6") (pintype "passive"))
      (node (ref "R13") (pin "1") (pinfunction "1_1") (pintype "passive"))
      (node (ref "U$2") (pin "42") (pinfunction "PB6USART1_TX/I2C1_SCL_42") (pintype "bidirectional"))
      (node (ref "U$7") (pin "3") (pinfunction "C3_3") (pintype "bidirectional"))
    )
    (net (code "30") (name "/KC4") (class "Default")
      (node (ref "JP3") (pin "5") (pinfunction "5_5") (pintype "passive"))
      (node (ref "R14") (pin "1") (pinfunction "1_1") (pintype "passive"))
      (node (ref "U$2") (pin "45") (pinfunction "PB8/I2C1_SCL/TIM16_CH1/CAN_RX_45") (pintype "bidirectional"))
      (node (ref "U$7") (pin "4") (pinfunction "C4_4") (pintype "bidirectional"))
    )
    (net (code "31") (name "/KEYB_DM") (class "Default")
      (node (ref "U$2") (pin "32") (pinfunction "PA11/USB_DM/CAN_RX_32") (pintype "bidirectional"))
      (node (ref "USB") (pin "4") (pinfunction "DM4_4") (pintype "bidirectional"))
    )
    (net (code "32") (name "/KEYB_DP") (class "Default")
      (node (ref "U$2") (pin "33") (pinfunction "PA12/USB_DP/CAN_TX_33") (pintype "bidirectional"))
      (node (ref "USB") (pin "5") (pinfunction "DP4_5") (pintype "bidirectional"))
    )
    (net (code "33") (name "/KMCU_RX") (class "Default")
      (node (ref "R76") (pin "1") (pinfunction "1_1") (pintype "passive"))
      (node (ref "U$2") (pin "31") (pinfunction "PA10/USART1_RX/TIM1_CH3_31") (pintype "bidirectional"))
    )
    (net (code "34") (name "/KMCU_TX") (class "Default")
      (node (ref "R75") (pin "1") (pinfunction "1_1") (pintype "passive"))
      (node (ref "U$2") (pin "30") (pinfunction "PA9/USART1_TX/TIM1_CH2_30") (pintype "bidirectional"))
    )
    (net (code "35") (name "/KR1") (class "Default")
      (node (ref "JP3") (pin "4") (pinfunction "4_4") (pintype "passive"))
      (node (ref "U$2") (pin "46") (pinfunction "PB9/I2C1_SDA/TIM17_CH1/CAN_TX_46") (pintype "bidirectional"))
      (node (ref "U$7") (pin "5") (pinfunction "R1_5") (pintype "bidirectional"))
    )
    (net (code "36") (name "/KR2") (class "Default")
      (node (ref "JP3") (pin "3") (pinfunction "3_3") (pintype "passive"))
      (node (ref "U$2") (pin "2") (pinfunction "PC13/WKUP2/RTC_TAMP1/RTC_TS/RTC_OUT_2") (pintype "bidirectional"))
      (node (ref "U$7") (pin "6") (pinfunction "R2_6") (pintype "bidirectional"))
    )
    (net (code "37") (name "/KR3") (class "Default")
      (node (ref "JP3") (pin "2") (pinfunction "2_2") (pintype "passive"))
      (node (ref "U$2") (pin "3") (pinfunction "PC14/OSC32_IN_3") (pintype "bidirectional"))
      (node (ref "U$7") (pin "7") (pinfunction "R3_7") (pintype "bidirectional"))
    )
    (net (code "38") (name "/KR4") (class "Default")
      (node (ref "JP3") (pin "1") (pinfunction "1_1") (pintype "passive"))
      (node (ref "U$2") (pin "4") (pinfunction "PC15/OSC32_OUT_4") (pintype "bidirectional"))
      (node (ref "U$7") (pin "8") (pinfunction "R4_8") (pintype "bidirectional"))
    )
    (net (code "39") (name "/LED1") (class "Default")
      (node (ref "JP8") (pin "1") (pinfunction "1_1") (pintype "passive"))
      (node (ref "U$2") (pin "13") (pinfunction "PA3/ADC_IN3/COMP2_INP/USART2_RX_13") (pintype "bidirectional"))
    )
    (net (code "40") (name "/LED2") (class "Default")
      (node (ref "JP8") (pin "2") (pinfunction "2_2") (pintype "passive"))
      (node (ref "U$2") (pin "14") (pinfunction "PA4/ADC_IN4/DAC_OUT1_14") (pintype "bidirectional"))
    )
    (net (code "41") (name "/LED3") (class "Default")
      (node (ref "JP8") (pin "3") (pinfunction "3_3") (pintype "passive"))
      (node (ref "U$12") (pin "9") (pinfunction "PA3_9") (pintype "bidirectional"))
    )
    (net (code "42") (name "/LED4") (class "Default")
      (node (ref "JP8") (pin "4") (pinfunction "4_4") (pintype "passive"))
      (node (ref "U$12") (pin "10") (pinfunction "PA4_10") (pintype "bidirectional"))
    )
    (net (code "43") (name "/MK1") (class "Default")
      (node (ref "K2") (pin "1A") (pinfunction "1A_1A") (pintype "bidirectional"))
      (node (ref "U$2") (pin "10") (pinfunction "PA0/USART4_TX/WKUP1/ADC_IN0_10") (pintype "bidirectional"))
    )
    (net (code "44") (name "/MK2") (class "Default")
      (node (ref "K3") (pin "1B") (pinfunction "1B_1B") (pintype "bidirectional"))
      (node (ref "U$2") (pin "11") (pinfunction "PA1/ADC_IN1/COMP1_INP/USART4_RX_11") (pintype "bidirectional"))
    )
    (net (code "45") (name "/MK3") (class "Default")
      (node (ref "K1") (pin "1A") (pinfunction "1A_1A") (pintype "bidirectional"))
      (node (ref "R15") (pin "2") (pinfunction "2_2") (pintype "passive"))
      (node (ref "U$2") (pin "12") (pinfunction "PA2/ADC_IN2/WKUP4USART2_TX_12") (pintype "bidirectional"))
    )
    (net (code "46") (name "/PWM0") (class "Default")
      (node (ref "R27") (pin "2") (pinfunction "2_2") (pintype "passive"))
      (node (ref "U$11") (pin "12") (pinfunction "GPIO18_12") (pintype "bidirectional"))
    )
    (net (code "47") (name "/PWM1") (class "Default")
      (node (ref "R26") (pin "2") (pinfunction "2_2") (pintype "passive"))
      (node (ref "U$11") (pin "33") (pinfunction "GPIO13_33") (pintype "bidirectional"))
    )
    (net (code "48") (name "/RPG1") (class "Default")
      (node (ref "R56") (pin "1") (pinfunction "1_1") (pintype "passive"))
      (node (ref "U$11") (pin "35") (pinfunction "GPIO19_35") (pintype "bidirectional"))
    )
    (net (code "49") (name "/RPG2") (class "Default")
      (node (ref "R55") (pin "1") (pinfunction "1_1") (pintype "passive"))
      (node (ref "U$11") (pin "37") (pinfunction "GPIO26_37") (pintype "bidirectional"))
    )
    (net (code "50") (name "/RPRX") (class "Default")
      (node (ref "R57") (pin "1") (pinfunction "1_1") (pintype "passive"))
      (node (ref "U$11") (pin "10") (pinfunction "RXD0/GPIO15_10") (pintype "bidirectional"))
    )
    (net (code "51") (name "/RPTX") (class "Default")
      (node (ref "R58") (pin "1") (pinfunction "1_1") (pintype "passive"))
      (node (ref "U$11") (pin "8") (pinfunction "TXD0/GPIO14_8") (pintype "bidirectional"))
    )
    (net (code "52") (name "/RST") (class "Default")
      (node (ref "JP9") (pin "9") (pinfunction "9_9") (pintype "passive"))
      (node (ref "U$11") (pin "22") (pinfunction "GEN/6GPIO25_22") (pintype "bidirectional"))
    )
    (net (code "53") (name "/R_SCL") (class "Default")
      (node (ref "IC8") (pin "6") (pinfunction "SCL_6") (pintype "bidirectional"))
      (node (ref "R61") (pin "1") (pinfunction "1_1") (pintype "passive"))
      (node (ref "R9") (pin "1") (pinfunction "1_1") (pintype "passive"))
      (node (ref "U$11") (pin "5") (pinfunction "GPIO3/SCL1_5") (pintype "bidirectional"))
    )
    (net (code "54") (name "/R_SDA") (class "Default")
      (node (ref "IC8") (pin "5") (pinfunction "SDA_5") (pintype "bidirectional"))
      (node (ref "R10") (pin "1") (pinfunction "1_1") (pintype "passive"))
      (node (ref "R60") (pin "1") (pinfunction "1_1") (pintype "passive"))
      (node (ref "U$11") (pin "3") (pinfunction "GPIO2/SDA1_3") (pintype "bidirectional"))
    )
    (net (code "55") (name "/SCK") (class "Default")
      (node (ref "JP9") (pin "5") (pinfunction "5_5") (pintype "passive"))
      (node (ref "R63") (pin "1") (pinfunction "1_1") (pintype "passive"))
    )
    (net (code "56") (name "/SCK_R") (class "Default")
      (node (ref "R63") (pin "2") (pinfunction "2_2") (pintype "passive"))
      (node (ref "U$11") (pin "23") (pinfunction "GPIO11/SCLK_23") (pintype "bidirectional"))
    )
    (net (code "57") (name "/SDA") (class "Default")
      (node (ref "JP9") (pin "6") (pinfunction "6_6") (pintype "passive"))
      (node (ref "U$11") (pin "19") (pinfunction "GPIO10/MOSI_19") (pintype "bidirectional"))
    )
    (net (code "58") (name "/V25A") (class "Default")
      (node (ref "C40") (pin "2") (pinfunction "2_2") (pintype "passive"))
      (node (ref "IC10") (pin "2") (pinfunction "OUT_2") (pintype "output"))
      (node (ref "IC9") (pin "5") (pinfunction "VDD_5") (pintype "bidirectional"))
    )
    (net (code "59") (name "/V50A") (class "Default")
      (node (ref "C34") (pin "2") (pinfunction "2_2") (pintype "passive"))
      (node (ref "C43") (pin "+") (pinfunction "+_+") (pintype "passive"))
      (node (ref "R29") (pin "1") (pinfunction "1_1") (pintype "passive"))
      (node (ref "R33") (pin "2") (pinfunction "2_2") (pintype "passive"))
      (node (ref "R35") (pin "1") (pinfunction "1_1") (pintype "passive"))
      (node (ref "U$9") (pin "8") (pinfunction "VDD_8") (pintype "bidirectional"))
    )
    (net (code "60") (name "/VBAT") (class "Default")
      (node (ref "IC1") (pin "7") (pinfunction "VBAT_7") (pintype "bidirectional"))
      (node (ref "PTC2") (pin "P$2") (pinfunction "2_P$2") (pintype "passive"))
      (node (ref "R53") (pin "2") (pinfunction "2_2") (pintype "passive"))
      (node (ref "T1") (pin "5") (pinfunction "D_5") (pintype "bidirectional"))
      (node (ref "T1") (pin "6") (pinfunction "D_6") (pintype "bidirectional"))
      (node (ref "T1") (pin "7") (pinfunction "D_7") (pintype "bidirectional"))
      (node (ref "T1") (pin "8") (pinfunction "D_8") (pintype "bidirectional"))
      (node (ref "T2") (pin "5") (pinfunction "D_5") (pintype "bidirectional"))
      (node (ref "T2") (pin "6") (pinfunction "D_6") (pintype "bidirectional"))
      (node (ref "T2") (pin "7") (pinfunction "D_7") (pintype "bidirectional"))
      (node (ref "T2") (pin "8") (pinfunction "D_8") (pintype "bidirectional"))
    )
    (net (code "61") (name "/WL_D+") (class "Default")
      (node (ref "MOD1") (pin "D+") (pinfunction "D+_D+") (pintype "bidirectional"))
      (node (ref "USB") (pin "7") (pinfunction "DP3_7") (pintype "bidirectional"))
    )
    (net (code "62") (name "/WL_D-") (class "Default")
      (node (ref "MOD1") (pin "D-") (pinfunction "D-_D-") (pintype "bidirectional"))
      (node (ref "USB") (pin "6") (pinfunction "DM3_6") (pintype "bidirectional"))
    )
    (net (code "63") (name "GND") (class "Default")
      (node (ref "C1") (pin "1") (pinfunction "1_1") (pintype "passive"))
      (node (ref "C10") (pin "2") (pinfunction "2_2") (pintype "passive"))
      (node (ref "C11") (pin "2") (pinfunction "2_2") (pintype "passive"))
      (node (ref "C12") (pin "2") (pinfunction "2_2") (pintype "passive"))
      (node (ref "C13") (pin "2") (pinfunction "2_2") (pintype "passive"))
      (node (ref "C14") (pin "2") (pinfunction "2_2") (pintype "passive"))
      (node (ref "C15") (pin "2") (pinfunction "2_2") (pintype "passive"))
      (node (ref "C16") (pin "2") (pinfunction "2_2") (pintype "passive"))
      (node (ref "C2") (pin "1") (pinfunction "1_1") (pintype "passive"))
      (node (ref "C20") (pin "2") (pinfunction "2_2") (pintype "passive"))
      (node (ref "C21") (pin "2") (pinfunction "2_2") (pintype "passive"))
      (node (ref "C22") (pin "2") (pinfunction "2_2") (pintype "passive"))
      (node (ref "C23") (pin "2") (pinfunction "2_2") (pintype "passive"))
      (node (ref "C24") (pin "2") (pinfunction "2_2") (pintype "passive"))
      (node (ref "C25") (pin "2") (pinfunction "2_2") (pintype "passive"))
      (node (ref "C26") (pin "2") (pinfunction "2_2") (pintype "passive"))
      (node (ref "C27") (pin "2") (pinfunction "2_2") (pintype "passive"))
      (node (ref "C28") (pin "2") (pinfunction "2_2") (pintype "passive"))
      (node (ref "C29") (pin "2") (pinfunction "2_2") (pintype "passive"))
      (node (ref "C3") (pin "2") (pinfunction "2_2") (pintype "passive"))
      (node (ref "C30") (pin "1") (pinfunction "1_1") (pintype "passive"))
      (node (ref "C32") (pin "1") (pinfunction "1_1") (pintype "passive"))
      (node (ref "C33") (pin "1") (pinfunction "1_1") (pintype "passive"))
      (node (ref "C34") (pin "1") (pinfunction "1_1") (pintype "passive"))
      (node (ref "C35") (pin "1") (pinfunction "1_1") (pintype "passive"))
      (node (ref "C37") (pin "1") (pinfunction "1_1") (pintype "passive"))
      (node (ref "C39") (pin "1") (pinfunction "1_1") (pintype "passive"))
      (node (ref "C4") (pin "2") (pinfunction "2_2") (pintype "passive"))
      (node (ref "C40") (pin "1") (pinfunction "1_1") (pintype "passive"))
      (node (ref "C41") (pin "1") (pinfunction "1_1") (pintype "passive"))
      (node (ref "C42") (pin "1") (pinfunction "1_1") (pintype "passive"))
      (node (ref "C43") (pin "-") (pinfunction "-_-") (pintype "passive"))
      (node (ref "C46") (pin "-") (pinfunction "-_-") (pintype "passive"))
      (node (ref "C47") (pin "-") (pinfunction "-_-") (pintype "passive"))
      (node (ref "C48") (pin "1") (pinfunction "1_1") (pintype "passive"))
      (node (ref "C49") (pin "1") (pinfunction "1_1") (pintype "passive"))
      (node (ref "C5") (pin "2") (pinfunction "2_2") (pintype "passive"))
      (node (ref "C50") (pin "1") (pinfunction "1_1") (pintype "passive"))
      (node (ref "C51") (pin "2") (pinfunction "2_2") (pintype "passive"))
      (node (ref "C6") (pin "2") (pinfunction "2_2") (pintype "passive"))
      (node (ref "C7") (pin "2") (pinfunction "2_2") (pintype "passive"))
      (node (ref "C8") (pin "2") (pinfunction "2_2") (pintype "passive"))
      (node (ref "C9") (pin "2") (pinfunction "2_2") (pintype "passive"))
      (node (ref "D1") (pin "A") (pinfunction "A_A") (pintype "passive"))
      (node (ref "GND") (pin "TP") (pinfunction "TP_TP") (pintype "input"))
      (node (ref "IC1") (pin "6") (pinfunction "GND_6") (pintype "bidirectional"))
      (node (ref "IC10") (pin "1") (pinfunction "VSS_1") (pintype "input"))
      (node (ref "IC11") (pin "2") (pinfunction "VSS_2") (pintype "power_in"))
      (node (ref "IC2") (pin "1") (pinfunction "VSS_1") (pintype "input"))
      (node (ref "IC3") (pin "1") (pinfunction "VSS_1") (pintype "input"))
      (node (ref "IC4") (pin "1") (pinfunction "GND_1") (pintype "bidirectional"))
      (node (ref "IC5") (pin "1") (pinfunction "GND_1") (pintype "bidirectional"))
      (node (ref "IC6") (pin "1") (pinfunction "GND_1") (pintype "bidirectional"))
      (node (ref "IC7") (pin "3") (pinfunction "~{WP}_3") (pintype "input"))
      (node (ref "IC7") (pin "4") (pinfunction "VSS_4") (pintype "power_in"))
      (node (ref "IC7") (pin "7") (pinfunction "~{HOLD}_7") (pintype "input"))
      (node (ref "IC8") (pin "4") (pinfunction "VSS_4") (pintype "bidirectional"))
      (node (ref "IC9") (pin "2") (pinfunction "GND_2") (pintype "bidirectional"))
      (node (ref "JP1") (pin "2") (pinfunction "2_2") (pintype "passive"))
      (node (ref "JP10") (pin "5") (pinfunction "5_5") (pintype "passive"))
      (node (ref "JP2") (pin "5") (pinfunction "5_5") (pintype "passive"))
      (node (ref "JP6") (pin "SLEEVE") (pinfunction "SLEEVE_SLEEVE") (pintype "bidirectional"))
      (node (ref "JP7") (pin "1") (pinfunction "1_1") (pintype "passive"))
      (node (ref "JP9") (pin "1") (pinfunction "1_1") (pintype "passive"))
      (node (ref "K1") (pin "1B") (pinfunction "1B_1B") (pintype "bidirectional"))
      (node (ref "K2") (pin "2B") (pinfunction "2B_2B") (pintype "bidirectional"))
      (node (ref "K3") (pin "2A") (pinfunction "2A_2A") (pintype "bidirectional"))
      (node (ref "K4") (pin "2B") (pinfunction "2B_2B") (pintype "bidirectional"))
      (node (ref "MOD1") (pin "GND") (pinfunction "GND_GND") (pintype "bidirectional"))
      (node (ref "MOD1") (pin "RFGND") (pinfunction "RFGND_RFGND") (pintype "bidirectional"))
      (node (ref "R18") (pin "1") (pinfunction "1_1") (pintype "passive"))
      (node (ref "R2") (pin "2") (pinfunction "2_2") (pintype "passive"))
      (node (ref "R20") (pin "1") (pinfunction "1_1") (pintype "passive"))
      (node (ref "R22") (pin "1") (pinfunction "1_1") (pintype "passive"))
      (node (ref "R24") (pin "1") (pinfunction "1_1") (pintype "passive"))
      (node (ref "R25") (pin "1") (pinfunction "1_1") (pintype "passive"))
      (node (ref "R28") (pin "1") (pinfunction "1_1") (pintype "passive"))
      (node (ref "R31") (pin "1") (pinfunction "1_1") (pintype "passive"))
      (node (ref "R32") (pin "1") (pinfunction "1_1") (pintype "passive"))
      (node (ref "R51") (pin "2") (pinfunction "2_2") (pintype "passive"))
      (node (ref "R52") (pin "2") (pinfunction "2_2") (pintype "passive"))
      (node (ref "R54") (pin "1") (pinfunction "1_1") (pintype "passive"))
      (node (ref "R70") (pin "1") (pinfunction "1_1") (pintype "passive"))
      (node (ref "R71") (pin "2") (pinfunction "2_2") (pintype "passive"))
      (node (ref "TP1") (pin "TP") (pinfunction "TP_TP") (pintype "input"))
      (node (ref "TP2") (pin "TP") (pinfunction "TP_TP") (pintype "input"))
      (node (ref "TP3") (pin "TP") (pinfunction "TP_TP") (pintype "input"))
      (node (ref "TP4") (pin "TP") (pinfunction "TP_TP") (pintype "input"))
      (node (ref "U$1") (pin "2") (pinfunction "N_2") (pintype "bidirectional"))
      (node (ref "U$1") (pin "3") (pinfunction "SW_3") (pintype "bidirectional"))
      (node (ref "U$10") (pin "G") (pinfunction "G_G") (pintype "bidirectional"))
      (node (ref "U$11") (pin "14") (pinfunction "GND_14") (pintype "power_in"))
      (node (ref "U$11") (pin "20") (pinfunction "GND_20") (pintype "power_in"))
      (node (ref "U$11") (pin "25") (pinfunction "GND_25") (pintype "power_in"))
      (node (ref "U$11") (pin "30") (pinfunction "GND_30") (pintype "power_in"))
      (node (ref "U$11") (pin "34") (pinfunction "GND_34") (pintype "power_in"))
      (node (ref "U$11") (pin "39") (pinfunction "GND_39") (pintype "power_in"))
      (node (ref "U$11") (pin "9") (pinfunction "GND_9") (pintype "power_in"))
      (node (ref "U$12") (pin "15") (pinfunction "VSS_15") (pintype "bidirectional"))
      (node (ref "U$2") (pin "23") (pinfunction "VSS_1(P23)_23") (pintype "bidirectional"))
      (node (ref "U$2") (pin "35") (pinfunction "VSS_2(P35)_35") (pintype "bidirectional"))
      (node (ref "U$2") (pin "47") (pinfunction "VSS_3(P47)_47") (pintype "bidirectional"))
      (node (ref "U$2") (pin "8") (pinfunction "VSSA(P8)_8") (pintype "bidirectional"))
      (node (ref "U$9") (pin "4") (pinfunction "GND_4") (pintype "bidirectional"))
      (node (ref "USB") (pin "1") (pinfunction "VSS_1") (pintype "bidirectional"))
      (node (ref "USB1") (pin "GND") (pinfunction "GND_GND") (pintype "bidirectional"))
      (node (ref "USB1") (pin "GND@1") (pinfunction "GND_GND@1") (pintype "bidirectional"))
      (node (ref "USB1") (pin "GND@2") (pinfunction "GND_GND@2") (pintype "bidirectional"))
      (node (ref "USB2") (pin "GND") (pinfunction "GND_GND") (pintype "bidirectional"))
      (node (ref "USB2") (pin "GND@1") (pinfunction "GND_GND@1") (pintype "bidirectional"))
      (node (ref "USB2") (pin "GND@2") (pinfunction "GND_GND@2") (pintype "bidirectional"))
      (node (ref "X6") (pin "3") (pinfunction "S_3") (pintype "passive"))
    )
    (net (code "64") (name "Net-(ANT1-P$1)") (class "Default")
      (node (ref "ANT1") (pin "1") (pinfunction "P$1_1") (pintype "bidirectional"))
      (node (ref "MOD1") (pin "ANT") (pinfunction "ANT_ANT") (pintype "bidirectional"))
    )
    (net (code "65") (name "Net-(C31-Pad+)") (class "Default")
      (node (ref "C31") (pin "+") (pinfunction "+_+") (pintype "passive"))
      (node (ref "C42") (pin "2") (pinfunction "2_2") (pintype "passive"))
      (node (ref "R40") (pin "1") (pinfunction "1_1") (pintype "passive"))
    )
    (net (code "66") (name "Net-(C31-Pad-)") (class "Default")
      (node (ref "C31") (pin "-") (pinfunction "-_-") (pintype "passive"))
      (node (ref "U$10") (pin "T2") (pinfunction "T2_T2") (pintype "bidirectional"))
    )
    (net (code "67") (name "Net-(C36-Pad+)") (class "Default")
      (node (ref "C36") (pin "+") (pinfunction "+_+") (pintype "passive"))
      (node (ref "R39") (pin "1") (pinfunction "1_1") (pintype "passive"))
    )
    (net (code "68") (name "Net-(C36-Pad-)") (class "Default")
      (node (ref "C36") (pin "-") (pinfunction "-_-") (pintype "passive"))
      (node (ref "U$10") (pin "W2") (pinfunction "W2_W2") (pintype "bidirectional"))
    )
    (net (code "69") (name "Net-(C38-Pad+)") (class "Default")
      (node (ref "C38") (pin "+") (pinfunction "+_+") (pintype "passive"))
      (node (ref "R38") (pin "1") (pinfunction "1_1") (pintype "passive"))
    )
    (net (code "70") (name "Net-(C38-Pad-)") (class "Default")
      (node (ref "C38") (pin "-") (pinfunction "-_-") (pintype "passive"))
      (node (ref "U$10") (pin "W1") (pinfunction "W1_W1") (pintype "bidirectional"))
    )
    (net (code "71") (name "Net-(C41-Pad2)") (class "Default")
      (node (ref "C41") (pin "2") (pinfunction "2_2") (pintype "passive"))
      (node (ref "C52") (pin "+") (pinfunction "+_+") (pintype "passive"))
      (node (ref "R41") (pin "1") (pinfunction "1_1") (pintype "passive"))
    )
    (net (code "72") (name "Net-(C48-Pad2)") (class "Default")
      (node (ref "C48") (pin "2") (pinfunction "2_2") (pintype "passive"))
      (node (ref "MOD1") (pin "3V3") (pinfunction "3V3_3V3") (pintype "bidirectional"))
      (node (ref "R62") (pin "2") (pinfunction "2_2") (pintype "passive"))
    )
    (net (code "73") (name "Net-(C52-Pad-)") (class "Default")
      (node (ref "C52") (pin "-") (pinfunction "-_-") (pintype "passive"))
      (node (ref "U$10") (pin "T1") (pinfunction "T1_T1") (pintype "bidirectional"))
    )
    (net (code "74") (name "Net-(IC1-DRV)") (class "Default")
      (node (ref "IC1") (pin "8") (pinfunction "DRV_8") (pintype "bidirectional"))
      (node (ref "T1") (pin "4") (pinfunction "G_4") (pintype "bidirectional"))
    )
    (net (code "75") (name "Net-(IC1-EN)") (class "Default")
      (node (ref "IC1") (pin "4") (pinfunction "EN_4") (pintype "bidirectional"))
      (node (ref "R4") (pin "2") (pinfunction "2_2") (pintype "passive"))
    )
    (net (code "76") (name "Net-(IC1-SEN)") (class "Default")
      (node (ref "IC1") (pin "1") (pinfunction "SEN_1") (pintype "bidirectional"))
      (node (ref "R3") (pin "2") (pinfunction "2_2") (pintype "passive"))
      (node (ref "T1") (pin "1") (pinfunction "S_1") (pintype "bidirectional"))
      (node (ref "T1") (pin "2") (pinfunction "S_2") (pintype "bidirectional"))
      (node (ref "T1") (pin "3") (pinfunction "S_3") (pintype "bidirectional"))
    )
    (net (code "77") (name "Net-(IC1-STAT)") (class "Default")
      (node (ref "IC1") (pin "3") (pinfunction "STAT_3") (pintype "bidirectional"))
      (node (ref "R5") (pin "1") (pinfunction "1_1") (pintype "passive"))
    )
    (net (code "78") (name "Net-(IC1-TMR)") (class "Default")
      (node (ref "C5") (pin "1") (pinfunction "1_1") (pintype "passive"))
      (node (ref "IC1") (pin "5") (pinfunction "TMR_5") (pintype "bidirectional"))
    )
    (net (code "79") (name "Net-(IC1-VDD)") (class "Default")
      (node (ref "D2") (pin "C") (pinfunction "C_C") (pintype "passive"))
      (node (ref "IC1") (pin "2") (pinfunction "VDD_2") (pintype "bidirectional"))
      (node (ref "R3") (pin "1") (pinfunction "1_1") (pintype "passive"))
      (node (ref "R4") (pin "1") (pinfunction "1_1") (pintype "passive"))
    )
    (net (code "80") (name "Net-(IC2-IN)") (class "Default")
      (node (ref "C3") (pin "1") (pinfunction "1_1") (pintype "passive"))
      (node (ref "IC2") (pin "3") (pinfunction "IN_3") (pintype "input"))
      (node (ref "R6") (pin "1") (pinfunction "1_1") (pintype "passive"))
    )
    (net (code "81") (name "Net-(IC3-IN)") (class "Default")
      (node (ref "C4") (pin "1") (pinfunction "1_1") (pintype "passive"))
      (node (ref "IC3") (pin "3") (pinfunction "IN_3") (pintype "input"))
      (node (ref "R7") (pin "2") (pinfunction "2_2") (pintype "passive"))
    )
    (net (code "82") (name "Net-(IC4-SW)") (class "Default")
      (node (ref "C17") (pin "2") (pinfunction "2_2") (pintype "passive"))
      (node (ref "IC4") (pin "2") (pinfunction "SW_2") (pintype "bidirectional"))
      (node (ref "U$3") (pin "P$1") (pinfunction "P$1_P$1") (pintype "bidirectional"))
    )
    (net (code "83") (name "Net-(IC4-VBST)") (class "Default")
      (node (ref "C17") (pin "1") (pinfunction "1_1") (pintype "passive"))
      (node (ref "IC4") (pin "6") (pinfunction "VBST_6") (pintype "bidirectional"))
    )
    (net (code "84") (name "Net-(IC4-VFB)") (class "Default")
      (node (ref "IC4") (pin "4") (pinfunction "VFB_4") (pintype "bidirectional"))
      (node (ref "R19") (pin "2") (pinfunction "2_2") (pintype "passive"))
      (node (ref "R20") (pin "2") (pinfunction "2_2") (pintype "passive"))
    )
    (net (code "85") (name "Net-(IC5-SW)") (class "Default")
      (node (ref "C18") (pin "2") (pinfunction "2_2") (pintype "passive"))
      (node (ref "IC5") (pin "2") (pinfunction "SW_2") (pintype "bidirectional"))
      (node (ref "U$4") (pin "P$1") (pinfunction "P$1_P$1") (pintype "bidirectional"))
    )
    (net (code "86") (name "Net-(IC5-VBST)") (class "Default")
      (node (ref "C18") (pin "1") (pinfunction "1_1") (pintype "passive"))
      (node (ref "IC5") (pin "6") (pinfunction "VBST_6") (pintype "bidirectional"))
    )
    (net (code "87") (name "Net-(IC5-VFB)") (class "Default")
      (node (ref "IC5") (pin "4") (pinfunction "VFB_4") (pintype "bidirectional"))
      (node (ref "R21") (pin "2") (pinfunction "2_2") (pintype "passive"))
      (node (ref "R22") (pin "2") (pinfunction "2_2") (pintype "passive"))
    )
    (net (code "88") (name "Net-(IC6-SW)") (class "Default")
      (node (ref "C19") (pin "2") (pinfunction "2_2") (pintype "passive"))
      (node (ref "IC6") (pin "2") (pinfunction "SW_2") (pintype "bidirectional"))
      (node (ref "U$5") (pin "P$1") (pinfunction "P$1_P$1") (pintype "bidirectional"))
    )
    (net (code "89") (name "Net-(IC6-VBST)") (class "Default")
      (node (ref "C19") (pin "1") (pinfunction "1_1") (pintype "passive"))
      (node (ref "IC6") (pin "6") (pinfunction "VBST_6") (pintype "bidirectional"))
    )
    (net (code "90") (name "Net-(IC6-VFB)") (class "Default")
      (node (ref "IC6") (pin "4") (pinfunction "VFB_4") (pintype "bidirectional"))
      (node (ref "R23") (pin "2") (pinfunction "2_2") (pintype "passive"))
      (node (ref "R24") (pin "2") (pinfunction "2_2") (pintype "passive"))
    )
    (net (code "91") (name "Net-(IC7-SCK)") (class "Default")
      (node (ref "IC7") (pin "6") (pinfunction "SCK_6") (pintype "input"))
      (node (ref "U$2") (pin "26") (pinfunction "PB13/SPI2_SCK/I2C2_SCL_26") (pintype "bidirectional"))
    )
    (net (code "92") (name "Net-(IC7-SI)") (class "Default")
      (node (ref "IC7") (pin "5") (pinfunction "SI_5") (pintype "input"))
      (node (ref "U$2") (pin "28") (pinfunction "PB15/WKUP7/RTC_REFIN/SPI2_MOSI_28") (pintype "bidirectional"))
    )
    (net (code "93") (name "Net-(IC7-SO)") (class "Default")
      (node (ref "IC7") (pin "2") (pinfunction "SO_2") (pintype "input"))
      (node (ref "U$2") (pin "27") (pinfunction "PB14/SPI2_MISO/I2C2_SDA_27") (pintype "bidirectional"))
    )
    (net (code "94") (name "Net-(IC7-~{CS})") (class "Default")
      (node (ref "IC7") (pin "1") (pinfunction "~{CS}_1") (pintype "input"))
      (node (ref "R8") (pin "2") (pinfunction "2_2") (pintype "passive"))
      (node (ref "U$2") (pin "29") (pinfunction "PA8/TIM1_CH1_29") (pintype "bidirectional"))
    )
    (net (code "95") (name "Net-(IC8-OSI)") (class "Default")
      (node (ref "IC8") (pin "1") (pinfunction "OSI_1") (pintype "bidirectional"))
      (node (ref "Q1") (pin "1") (pinfunction "1_1") (pintype "bidirectional"))
    )
    (net (code "96") (name "Net-(IC8-OSO)") (class "Default")
      (node (ref "IC8") (pin "2") (pinfunction "OSO_2") (pintype "bidirectional"))
      (node (ref "Q1") (pin "4") (pinfunction "2_4") (pintype "bidirectional"))
    )
    (net (code "97") (name "Net-(IC8-VBAT)") (class "Default")
      (node (ref "IC8") (pin "3") (pinfunction "VBAT_3") (pintype "bidirectional"))
      (node (ref "U$6") (pin "POS") (pinfunction "P_POS") (pintype "bidirectional"))
    )
    (net (code "98") (name "Net-(IC9-1A)") (class "Default")
      (node (ref "IC9") (pin "1") (pinfunction "1A_1") (pintype "bidirectional"))
      (node (ref "R26") (pin "1") (pinfunction "1_1") (pintype "passive"))
      (node (ref "R28") (pin "2") (pinfunction "2_2") (pintype "passive"))
    )
    (net (code "99") (name "Net-(IC9-1Y)") (class "Default")
      (node (ref "IC9") (pin "6") (pinfunction "1Y_6") (pintype "bidirectional"))
      (node (ref "R40") (pin "2") (pinfunction "2_2") (pintype "passive"))
    )
    (net (code "100") (name "Net-(IC9-2A)") (class "Default")
      (node (ref "IC9") (pin "3") (pinfunction "2A_3") (pintype "bidirectional"))
      (node (ref "R27") (pin "1") (pinfunction "1_1") (pintype "passive"))
      (node (ref "R31") (pin "2") (pinfunction "2_2") (pintype "passive"))
    )
    (net (code "101") (name "Net-(IC9-2Y)") (class "Default")
      (node (ref "IC9") (pin "4") (pinfunction "2Y_4") (pintype "bidirectional"))
      (node (ref "R41") (pin "2") (pinfunction "2_2") (pintype "passive"))
    )
    (net (code "102") (name "Net-(IC10-IN)") (class "Default")
      (node (ref "C39") (pin "2") (pinfunction "2_2") (pintype "passive"))
      (node (ref "IC10") (pin "3") (pinfunction "IN_3") (pintype "input"))
      (node (ref "R35") (pin "2") (pinfunction "2_2") (pintype "passive"))
    )
    (net (code "103") (name "Net-(IC11A-IN-)") (class "Default")
      (node (ref "IC11") (pin "1") (pinfunction "VYSTUP_1") (pintype "output"))
      (node (ref "IC11") (pin "4") (pinfunction "IN-_4") (pintype "input"))
      (node (ref "R59") (pin "2") (pinfunction "2_2") (pintype "passive"))
    )
    (net (code "104") (name "Net-(IC11A-NEIN+)") (class "Default")
      (node (ref "IC11") (pin "3") (pinfunction "NEIN+_3") (pintype "input"))
      (node (ref "R53") (pin "1") (pinfunction "1_1") (pintype "passive"))
      (node (ref "R54") (pin "2") (pinfunction "2_2") (pintype "passive"))
    )
    (net (code "105") (name "Net-(JP4-Pad3)") (class "Default")
      (node (ref "JP4") (pin "3") (pinfunction "3_3") (pintype "passive"))
      (node (ref "R30") (pin "2") (pinfunction "2_2") (pintype "passive"))
    )
    (net (code "106") (name "Net-(JP4-Pad4)") (class "Default")
      (node (ref "JP4") (pin "4") (pinfunction "4_4") (pintype "passive"))
      (node (ref "R36") (pin "1") (pinfunction "1_1") (pintype "passive"))
    )
    (net (code "107") (name "Net-(JP5-Pad1)") (class "Default")
      (node (ref "JP5") (pin "1") (pinfunction "1_1") (pintype "passive"))
      (node (ref "R49") (pin "2") (pinfunction "2_2") (pintype "passive"))
    )
    (net (code "108") (name "Net-(JP5-Pad2)") (class "Default")
      (node (ref "JP5") (pin "2") (pinfunction "2_2") (pintype "passive"))
      (node (ref "R48") (pin "2") (pinfunction "2_2") (pintype "passive"))
    )
    (net (code "109") (name "Net-(JP5-Pad3)") (class "Default")
      (node (ref "JP5") (pin "3") (pinfunction "3_3") (pintype "passive"))
      (node (ref "R47") (pin "2") (pinfunction "2_2") (pintype "passive"))
    )
    (net (code "110") (name "Net-(JP5-Pad4)") (class "Default")
      (node (ref "JP5") (pin "4") (pinfunction "4_4") (pintype "passive"))
      (node (ref "R46") (pin "2") (pinfunction "2_2") (pintype "passive"))
    )
    (net (code "111") (name "Net-(JP6-LEFT)") (class "Default")
      (node (ref "C44") (pin "-") (pinfunction "-_-") (pintype "passive"))
      (node (ref "JP6") (pin "TIP") (pinfunction "LEFT_TIP") (pintype "bidirectional"))
      (node (ref "R52") (pin "1") (pinfunction "1_1") (pintype "passive"))
    )
    (net (code "112") (name "Net-(JP6-RIGHT)") (class "Default")
      (node (ref "C45") (pin "-") (pinfunction "-_-") (pintype "passive"))
      (node (ref "JP6") (pin "RING") (pinfunction "RIGHT_RING") (pintype "bidirectional"))
      (node (ref "R51") (pin "1") (pinfunction "1_1") (pintype "passive"))
    )
    (net (code "113") (name "Net-(JP7-Pad2)") (class "Default")
      (node (ref "JP7") (pin "2") (pinfunction "2_2") (pintype "passive"))
      (node (ref "R64") (pin "1") (pinfunction "1_1") (pintype "passive"))
    )
    (net (code "114") (name "Net-(JP7-Pad4)") (class "Default")
      (node (ref "JP7") (pin "4") (pinfunction "4_4") (pintype "passive"))
      (node (ref "R65") (pin "1") (pinfunction "1_1") (pintype "passive"))
    )
    (net (code "115") (name "Net-(JP7-Pad6)") (class "Default")
      (node (ref "JP7") (pin "6") (pinfunction "6_6") (pintype "passive"))
      (node (ref "R66") (pin "1") (pinfunction "1_1") (pintype "passive"))
    )
    (net (code "116") (name "Net-(JP7-Pad7)") (class "Default")
      (node (ref "JP7") (pin "7") (pinfunction "7_7") (pintype "passive"))
      (node (ref "R60") (pin "2") (pinfunction "2_2") (pintype "passive"))
    )
    (net (code "117") (name "Net-(JP7-Pad8)") (class "Default")
      (node (ref "JP7") (pin "8") (pinfunction "8_8") (pintype "passive"))
      (node (ref "R67") (pin "1") (pinfunction "1_1") (pintype "passive"))
    )
    (net (code "118") (name "Net-(JP7-Pad9)") (class "Default")
      (node (ref "JP7") (pin "9") (pinfunction "9_9") (pintype "passive"))
      (node (ref "R61") (pin "2") (pinfunction "2_2") (pintype "passive"))
    )
    (net (code "119") (name "Net-(JP7-Pad10)") (class "Default")
      (node (ref "JP7") (pin "10") (pinfunction "10_10") (pintype "passive"))
      (node (ref "R68") (pin "1") (pinfunction "1_1") (pintype "passive"))
    )
    (net (code "120") (name "Net-(JP11-Pad1)") (class "Default")
      (node (ref "JP11") (pin "1") (pinfunction "1_1") (pintype "passive"))
      (node (ref "R75") (pin "2") (pinfunction "2_2") (pintype "passive"))
    )
    (net (code "121") (name "Net-(JP11-Pad2)") (class "Default")
      (node (ref "JP11") (pin "2") (pinfunction "2_2") (pintype "passive"))
      (node (ref "R76") (pin "2") (pinfunction "2_2") (pintype "passive"))
    )
    (net (code "122") (name "Net-(K2-Pad2A)") (class "Default")
      (node (ref "K2") (pin "2A") (pinfunction "2A_2A") (pintype "bidirectional"))
      (node (ref "R16") (pin "2") (pinfunction "2_2") (pintype "passive"))
    )
    (net (code "123") (name "Net-(K3-Pad2B)") (class "Default")
      (node (ref "K3") (pin "2B") (pinfunction "2B_2B") (pintype "bidirectional"))
      (node (ref "R17") (pin "2") (pinfunction "2_2") (pintype "passive"))
    )
    (net (code "124") (name "Net-(LED1-C)") (class "Default")
      (node (ref "JP4") (pin "1") (pinfunction "1_1") (pintype "passive"))
      (node (ref "LED1") (pin "K") (pinfunction "C_K") (pintype "passive"))
      (node (ref "LED2") (pin "K") (pinfunction "C_K") (pintype "passive"))
      (node (ref "LED3") (pin "K") (pinfunction "C_K") (pintype "passive"))
      (node (ref "LED4") (pin "K") (pinfunction "C_K") (pintype "passive"))
      (node (ref "LED5") (pin "C") (pinfunction "C_C") (pintype "passive"))
      (node (ref "LED6") (pin "C") (pinfunction "C_C") (pintype "passive"))
      (node (ref "LED7") (pin "C") (pinfunction "C_C") (pintype "passive"))
      (node (ref "LED8") (pin "C") (pinfunction "C_C") (pintype "passive"))
      (node (ref "T3") (pin "2") (pinfunction "E_2") (pintype "passive"))
      (node (ref "TFT1") (pin "1") (pinfunction "GND1_1") (pintype "bidirectional"))
      (node (ref "TFT1") (pin "8") (pinfunction "GND2_8") (pintype "bidirectional"))
    )
    (net (code "125") (name "Net-(LED1-PadA)") (class "Default")
      (node (ref "LED1") (pin "A") (pinfunction "A_A") (pintype "passive"))
      (node (ref "LED5") (pin "A") (pinfunction "A_A") (pintype "passive"))
      (node (ref "R46") (pin "1") (pinfunction "1_1") (pintype "passive"))
    )
    (net (code "126") (name "Net-(LED2-PadA)") (class "Default")
      (node (ref "LED2") (pin "A") (pinfunction "A_A") (pintype "passive"))
      (node (ref "LED6") (pin "A") (pinfunction "A_A") (pintype "passive"))
      (node (ref "R47") (pin "1") (pinfunction "1_1") (pintype "passive"))
    )
    (net (code "127") (name "Net-(LED3-PadA)") (class "Default")
      (node (ref "LED3") (pin "A") (pinfunction "A_A") (pintype "passive"))
      (node (ref "LED7") (pin "A") (pinfunction "A_A") (pintype "passive"))
      (node (ref "R48") (pin "1") (pinfunction "1_1") (pintype "passive"))
    )
    (net (code "128") (name "Net-(LED4-PadA)") (class "Default")
      (node (ref "LED4") (pin "A") (pinfunction "A_A") (pintype "passive"))
      (node (ref "LED8") (pin "A") (pinfunction "A_A") (pintype "passive"))
      (node (ref "R49") (pin "1") (pinfunction "1_1") (pintype "passive"))
    )
    (net (code "129") (name "Net-(PTC1-2)") (class "Default")
      (node (ref "PTC1") (pin "P$2") (pinfunction "2_P$2") (pintype "passive"))
      (node (ref "U$1") (pin "1") (pinfunction "P_1") (pintype "bidirectional"))
    )
    (net (code "130") (name "Net-(PTC2-1)") (class "Default")
      (node (ref "JP1") (pin "1") (pinfunction "1_1") (pintype "passive"))
      (node (ref "PTC2") (pin "P$1") (pinfunction "1_P$1") (pintype "passive"))
      (node (ref "X6") (pin "1") (pinfunction "S_1") (pintype "passive"))
    )
    (net (code "131") (name "Net-(PTC3-1)") (class "Default")
      (node (ref "JP7") (pin "3") (pinfunction "3_3") (pintype "passive"))
      (node (ref "PTC3") (pin "P$1") (pinfunction "1_P$1") (pintype "passive"))
    )
    (net (code "132") (name "Net-(PTC4-2)") (class "Default")
      (node (ref "JP7") (pin "5") (pinfunction "5_5") (pintype "passive"))
      (node (ref "PTC4") (pin "P$2") (pinfunction "2_P$2") (pintype "passive"))
    )
    (net (code "133") (name "Net-(PTC5-1)") (class "Default")
      (node (ref "C46") (pin "+") (pinfunction "+_+") (pintype "passive"))
      (node (ref "C47") (pin "+") (pinfunction "+_+") (pintype "passive"))
      (node (ref "PTC5") (pin "P$1") (pinfunction "1_P$1") (pintype "passive"))
      (node (ref "USB1") (pin "VBUS") (pinfunction "VBUS_VBUS") (pintype "bidirectional"))
      (node (ref "USB2") (pin "VBUS") (pinfunction "VBUS_VBUS") (pintype "bidirectional"))
    )
    (net (code "134") (name "Net-(PTC5-2)") (class "Default")
      (node (ref "PTC5") (pin "P$2") (pinfunction "2_P$2") (pintype "passive"))
      (node (ref "R50") (pin "1") (pinfunction "1_1") (pintype "passive"))
    )
    (net (code "135") (name "Net-(T3-B)") (class "Default")
      (node (ref "R36") (pin "2") (pinfunction "2_2") (pintype "passive"))
      (node (ref "R37") (pin "1") (pinfunction "1_1") (pintype "passive"))
      (node (ref "T3") (pin "1") (pinfunction "B_1") (pintype "passive"))
    )
    (net (code "136") (name "Net-(T3-C)") (class "Default")
      (node (ref "T3") (pin "3") (pinfunction "C_3") (pintype "passive"))
      (node (ref "TFT1") (pin "11") (pinfunction "LEDK1_11") (pintype "bidirectional"))
      (node (ref "TFT1") (pin "12") (pinfunction "LEDK2_12") (pintype "bidirectional"))
      (node (ref "TFT1") (pin "13") (pinfunction "LEDK3_13") (pintype "bidirectional"))
      (node (ref "TFT1") (pin "14") (pinfunction "LEDK4_14") (pintype "bidirectional"))
    )
    (net (code "137") (name "Net-(TFT1-CS)") (class "Default")
      (node (ref "JP4") (pin "7") (pinfunction "7_7") (pintype "passive"))
      (node (ref "TFT1") (pin "5") (pinfunction "CS_5") (pintype "bidirectional"))
    )
    (net (code "138") (name "Net-(TFT1-D{slash}C)") (class "Default")
      (node (ref "JP4") (pin "8") (pinfunction "8_8") (pintype "passive"))
      (node (ref "TFT1") (pin "4") (pinfunction "D/C_4") (pintype "bidirectional"))
    )
    (net (code "139") (name "Net-(TFT1-LEDA)") (class "Default")
      (node (ref "R30") (pin "1") (pinfunction "1_1") (pintype "passive"))
      (node (ref "TFT1") (pin "10") (pinfunction "LEDA_10") (pintype "bidirectional"))
    )
    (net (code "140") (name "Net-(TFT1-RST)") (class "Default")
      (node (ref "JP4") (pin "9") (pinfunction "9_9") (pintype "passive"))
      (node (ref "TFT1") (pin "2") (pinfunction "RST_2") (pintype "bidirectional"))
    )
    (net (code "141") (name "Net-(TFT1-SCK)") (class "Default")
      (node (ref "JP4") (pin "5") (pinfunction "5_5") (pintype "passive"))
      (node (ref "TFT1") (pin "3") (pinfunction "SCK_3") (pintype "bidirectional"))
    )
    (net (code "142") (name "Net-(TFT1-SDA)") (class "Default")
      (node (ref "JP4") (pin "6") (pinfunction "6_6") (pintype "passive"))
      (node (ref "TFT1") (pin "6") (pinfunction "SDA_6") (pintype "bidirectional"))
    )
    (net (code "143") (name "Net-(TFT1-VDD)") (class "Default")
      (node (ref "JP4") (pin "2") (pinfunction "2_2") (pintype "passive"))
      (node (ref "R37") (pin "2") (pinfunction "2_2") (pintype "passive"))
      (node (ref "TFT1") (pin "9") (pinfunction "VDD_9") (pintype "bidirectional"))
    )
    (net (code "144") (name "Net-(U$2-BOOT0(P44))") (class "Default")
      (node (ref "R2") (pin "1") (pinfunction "1_1") (pintype "passive"))
      (node (ref "U$2") (pin "44") (pinfunction "BOOT0(P44)_44") (pintype "bidirectional"))
    )
    (net (code "145") (name "Net-(U$2-NRST(P7))") (class "Default")
      (node (ref "JP2") (pin "2") (pinfunction "2_2") (pintype "passive"))
      (node (ref "R1") (pin "1") (pinfunction "1_1") (pintype "passive"))
      (node (ref "U$2") (pin "7") (pinfunction "NRST(P7)_7") (pintype "bidirectional"))
    )
    (net (code "146") (name "Net-(U$2-PA5{slash}ADC_IN5{slash}DAC_OUT2{slash}SPI1_SCK)") (class "Default")
      (node (ref "U$2") (pin "15") (pinfunction "PA5/ADC_IN5/DAC_OUT2/SPI1_SCK_15") (pintype "bidirectional"))
      (node (ref "X7") (pin "TP") (pinfunction "TP_TP") (pintype "input"))
    )
    (net (code "147") (name "Net-(U$2-PA6{slash}ADC_IN6{slash}SPI1_MISO{slash}TIM3_CH1)") (class "Default")
      (node (ref "U$2") (pin "16") (pinfunction "PA6/ADC_IN6/SPI1_MISO/TIM3_CH1_16") (pintype "bidirectional"))
      (node (ref "X8") (pin "TP") (pinfunction "TP_TP") (pintype "input"))
    )
    (net (code "148") (name "Net-(U$2-PA7{slash}ADC_IN7{slash}SPI1_MOSI{slash}TIM3_CH2)") (class "Default")
      (node (ref "U$2") (pin "17") (pinfunction "PA7/ADC_IN7/SPI1_MOSI/TIM3_CH2_17") (pintype "bidirectional"))
      (node (ref "X9") (pin "TP") (pinfunction "TP_TP") (pintype "input"))
    )
    (net (code "149") (name "Net-(U$2-PA13{slash}SWDIO)") (class "Default")
      (node (ref "JP2") (pin "1") (pinfunction "1_1") (pintype "passive"))
      (node (ref "U$2") (pin "34") (pinfunction "PA13/SWDIO_34") (pintype "bidirectional"))
    )
    (net (code "150") (name "Net-(U$2-PA14{slash}USART2_TX{slash}SWCLK)") (class "Default")
      (node (ref "JP2") (pin "3") (pinfunction "3_3") (pintype "passive"))
      (node (ref "U$2") (pin "37") (pinfunction "PA14/USART2_TX/SWCLK_37") (pintype "bidirectional"))
    )
    (net (code "151") (name "Net-(U$2-PA15{slash}USART2_RX)") (class "Default")
      (node (ref "U$2") (pin "38") (pinfunction "PA15/USART2_RX_38") (pintype "bidirectional"))
      (node (ref "X12") (pin "TP") (pinfunction "TP_TP") (pintype "input"))
    )
    (net (code "152") (name "Net-(U$2-PB3{slash}SPI1_SCK{slash}TIM2_CH2)") (class "Default")
      (node (ref "U$2") (pin "39") (pinfunction "PB3/SPI1_SCK/TIM2_CH2_39") (pintype "bidirectional"))
      (node (ref "X13") (pin "TP") (pinfunction "TP_TP") (pintype "input"))
    )
    (net (code "153") (name "Net-(U$2-PF0{slash}OSC_IN)") (class "Default")
      (node (ref "C1") (pin "2") (pinfunction "2_2") (pintype "passive"))
      (node (ref "U$2") (pin "5") (pinfunction "PF0/OSC_IN_5") (pintype "bidirectional"))
      (node (ref "X2") (pin "P$1") (pinfunction "P$1_P$1") (pintype "bidirectional"))
    )
    (net (code "154") (name "Net-(U$2-PF1{slash}OSC_OUT)") (class "Default")
      (node (ref "C2") (pin "2") (pinfunction "2_2") (pintype "passive"))
      (node (ref "U$2") (pin "6") (pinfunction "PF1/OSC_OUT_6") (pintype "bidirectional"))
      (node (ref "X2") (pin "P$2") (pinfunction "P$2_P$2") (pintype "bidirectional"))
    )
    (net (code "155") (name "Net-(U$6-M)") (class "Default")
      (node (ref "R18") (pin "2") (pinfunction "2_2") (pintype "passive"))
      (node (ref "U$6") (pin "N") (pinfunction "M_N") (pintype "bidirectional"))
    )
    (net (code "156") (name "Net-(U$9-IN1+)") (class "Default")
      (node (ref "C51") (pin "1") (pinfunction "1_1") (pintype "passive"))
      (node (ref "R25") (pin "2") (pinfunction "2_2") (pintype "passive"))
      (node (ref "R33") (pin "1") (pinfunction "1_1") (pintype "passive"))
      (node (ref "U$9") (pin "3") (pinfunction "IN1+_3") (pintype "bidirectional"))
      (node (ref "U$9") (pin "5") (pinfunction "IN2+_5") (pintype "bidirectional"))
    )
    (net (code "157") (name "Net-(U$9-IN1-)") (class "Default")
      (node (ref "R38") (pin "2") (pinfunction "2_2") (pintype "passive"))
      (node (ref "R42") (pin "1") (pinfunction "1_1") (pintype "passive"))
      (node (ref "U$9") (pin "2") (pinfunction "IN1-_2") (pintype "bidirectional"))
    )
    (net (code "158") (name "Net-(U$9-IN2-)") (class "Default")
      (node (ref "R39") (pin "2") (pinfunction "2_2") (pintype "passive"))
      (node (ref "R43") (pin "1") (pinfunction "1_1") (pintype "passive"))
      (node (ref "U$9") (pin "6") (pinfunction "IN2-_6") (pintype "bidirectional"))
    )
    (net (code "159") (name "Net-(U$9-OUT1)") (class "Default")
      (node (ref "C44") (pin "+") (pinfunction "+_+") (pintype "passive"))
      (node (ref "R42") (pin "2") (pinfunction "2_2") (pintype "passive"))
      (node (ref "U$9") (pin "1") (pinfunction "OUT1_1") (pintype "bidirectional"))
    )
    (net (code "160") (name "Net-(U$9-OUT2)") (class "Default")
      (node (ref "C45") (pin "+") (pinfunction "+_+") (pintype "passive"))
      (node (ref "R43") (pin "2") (pinfunction "2_2") (pintype "passive"))
      (node (ref "U$9") (pin "7") (pinfunction "OUT2_7") (pintype "bidirectional"))
    )
    (net (code "161") (name "Net-(U$12-BOOT0)") (class "Default")
      (node (ref "R71") (pin "1") (pinfunction "1_1") (pintype "passive"))
      (node (ref "U$12") (pin "1") (pinfunction "BOOT0_1") (pintype "bidirectional"))
    )
    (net (code "162") (name "Net-(U$12-PA6)") (class "Default")
      (node (ref "R55") (pin "2") (pinfunction "2_2") (pintype "passive"))
      (node (ref "U$12") (pin "12") (pinfunction "PA6_12") (pintype "bidirectional"))
    )
    (net (code "163") (name "Net-(U$12-PA9)") (class "Default")
      (node (ref "R57") (pin "2") (pinfunction "2_2") (pintype "passive"))
      (node (ref "U$12") (pin "17") (pinfunction "PA9_17") (pintype "bidirectional"))
    )
    (net (code "164") (name "Net-(U$12-PA10)") (class "Default")
      (node (ref "R58") (pin "2") (pinfunction "2_2") (pintype "passive"))
      (node (ref "U$12") (pin "18") (pinfunction "PA10_18") (pintype "bidirectional"))
    )
    (net (code "165") (name "Net-(U$12-PA13{slash}SWDIO)") (class "Default")
      (node (ref "JP10") (pin "1") (pinfunction "1_1") (pintype "passive"))
      (node (ref "U$12") (pin "19") (pinfunction "PA13/SWDIO_19") (pintype "bidirectional"))
    )
    (net (code "166") (name "Net-(U$12-PA14{slash}SWCLK)") (class "Default")
      (node (ref "JP10") (pin "3") (pinfunction "3_3") (pintype "passive"))
      (node (ref "U$12") (pin "20") (pinfunction "PA14/SWCLK_20") (pintype "bidirectional"))
    )
    (net (code "167") (name "Net-(U$12-PB1)") (class "Default")
      (node (ref "R56") (pin "2") (pinfunction "2_2") (pintype "passive"))
      (node (ref "U$12") (pin "14") (pinfunction "PB1_14") (pintype "bidirectional"))
    )
    (net (code "168") (name "Net-(U$12-PF1{slash}OSCO)") (class "Default")
      (node (ref "K4") (pin "1A") (pinfunction "1A_1A") (pintype "bidirectional"))
      (node (ref "R73") (pin "1") (pinfunction "1_1") (pintype "passive"))
      (node (ref "U$12") (pin "3") (pinfunction "PF1/OSCO_3") (pintype "bidirectional"))
    )
    (net (code "169") (name "Net-(U$12-~{RST})") (class "Default")
      (node (ref "JP10") (pin "2") (pinfunction "2_2") (pintype "passive"))
      (node (ref "R72") (pin "1") (pinfunction "1_1") (pintype "passive"))
      (node (ref "U$12") (pin "4") (pinfunction "~{RST}_4") (pintype "bidirectional"))
    )
    (net (code "170") (name "Net-(USB-BUSJ)") (class "Default")
      (node (ref "C33") (pin "2") (pinfunction "2_2") (pintype "passive"))
      (node (ref "USB") (pin "13") (pinfunction "VD33_13") (pintype "bidirectional"))
      (node (ref "USB") (pin "17") (pinfunction "XRSTJ_17") (pintype "bidirectional"))
      (node (ref "USB") (pin "18") (pinfunction "VBUSM_18") (pintype "bidirectional"))
      (node (ref "USB") (pin "19") (pinfunction "BUSJ_19") (pintype "bidirectional"))
      (node (ref "USB") (pin "21") (pinfunction "VD33_O_21") (pintype "bidirectional"))
      (node (ref "USB") (pin "26") (pinfunction "OVCJ_26") (pintype "bidirectional"))
    )
    (net (code "171") (name "Net-(USB-DM1)") (class "Default")
      (node (ref "USB") (pin "10") (pinfunction "DM1_10") (pintype "bidirectional"))
      (node (ref "USB1") (pin "D-") (pinfunction "D-_D-") (pintype "bidirectional"))
    )
    (net (code "172") (name "Net-(USB-DM2)") (class "Default")
      (node (ref "USB") (pin "8") (pinfunction "DM2_8") (pintype "bidirectional"))
      (node (ref "USB2") (pin "D-") (pinfunction "D-_D-") (pintype "bidirectional"))
    )
    (net (code "173") (name "Net-(USB-DP1)") (class "Default")
      (node (ref "USB") (pin "11") (pinfunction "DP1_11") (pintype "bidirectional"))
      (node (ref "USB1") (pin "D+") (pinfunction "D+_D+") (pintype "bidirectional"))
    )
    (net (code "174") (name "Net-(USB-DP2)") (class "Default")
      (node (ref "USB") (pin "9") (pinfunction "DP2_9") (pintype "bidirectional"))
      (node (ref "USB2") (pin "D+") (pinfunction "D+_D+") (pintype "bidirectional"))
    )
    (net (code "175") (name "Net-(USB-REXT)") (class "Default")
      (node (ref "R32") (pin "2") (pinfunction "2_2") (pintype "passive"))
      (node (ref "USB") (pin "14") (pinfunction "REXT_14") (pintype "bidirectional"))
    )
    (net (code "176") (name "Net-(USB-VD18)") (class "Default")
      (node (ref "C32") (pin "2") (pinfunction "2_2") (pintype "passive"))
      (node (ref "USB") (pin "12") (pinfunction "VD18_O_12") (pintype "bidirectional"))
      (node (ref "USB") (pin "28") (pinfunction "VD18_28") (pintype "bidirectional"))
    )
    (net (code "177") (name "Net-(USB-VDD5)") (class "Default")
      (node (ref "C35") (pin "2") (pinfunction "2_2") (pintype "passive"))
      (node (ref "R34") (pin "1") (pinfunction "1_1") (pintype "passive"))
      (node (ref "USB") (pin "20") (pinfunction "VDD5_20") (pintype "bidirectional"))
    )
    (net (code "178") (name "Net-(USB-XIN)") (class "Default")
      (node (ref "C37") (pin "2") (pinfunction "2_2") (pintype "passive"))
      (node (ref "USB") (pin "3") (pinfunction "XIN_3") (pintype "bidirectional"))
      (node (ref "X14") (pin "P$2") (pinfunction "P$2_P$2") (pintype "bidirectional"))
    )
    (net (code "179") (name "Net-(USB-XOUT)") (class "Default")
      (node (ref "C30") (pin "2") (pinfunction "2_2") (pintype "passive"))
      (node (ref "USB") (pin "2") (pinfunction "XOUT_2") (pintype "bidirectional"))
      (node (ref "X14") (pin "P$1") (pinfunction "P$1_P$1") (pintype "bidirectional"))
    )
    (net (code "180") (name "VCC") (class "Default")
      (node (ref "C10") (pin "1") (pinfunction "1_1") (pintype "passive"))
      (node (ref "C6") (pin "1") (pinfunction "1_1") (pintype "passive"))
      (node (ref "C8") (pin "1") (pinfunction "1_1") (pintype "passive"))
      (node (ref "C9") (pin "1") (pinfunction "1_1") (pintype "passive"))
      (node (ref "IC3") (pin "2") (pinfunction "OUT_2") (pintype "output"))
      (node (ref "IC7") (pin "8") (pinfunction "VDD_8") (pintype "power_in"))
      (node (ref "JP2") (pin "4") (pinfunction "4_4") (pintype "passive"))
      (node (ref "R1") (pin "2") (pinfunction "2_2") (pintype "passive"))
      (node (ref "R11") (pin "2") (pinfunction "2_2") (pintype "passive"))
      (node (ref "R12") (pin "2") (pinfunction "2_2") (pintype "passive"))
      (node (ref "R13") (pin "2") (pinfunction "2_2") (pintype "passive"))
      (node (ref "R14") (pin "2") (pinfunction "2_2") (pintype "passive"))
      (node (ref "R15") (pin "1") (pinfunction "1_1") (pintype "passive"))
      (node (ref "R16") (pin "1") (pinfunction "1_1") (pintype "passive"))
      (node (ref "R17") (pin "1") (pinfunction "1_1") (pintype "passive"))
      (node (ref "R8") (pin "1") (pinfunction "1_1") (pintype "passive"))
      (node (ref "U$2") (pin "1") (pinfunction "VBATT(P1)_1") (pintype "bidirectional"))
      (node (ref "U$2") (pin "24") (pinfunction "VDD_1(P24)_24") (pintype "bidirectional"))
      (node (ref "U$2") (pin "36") (pinfunction "VDDIO2(P36)_36") (pintype "bidirectional"))
      (node (ref "U$2") (pin "48") (pinfunction "VDD_2(P48)_48") (pintype "bidirectional"))
      (node (ref "U$2") (pin "9") (pinfunction "VDDA(P9)_9") (pintype "bidirectional"))
      (node (ref "VDD") (pin "TP") (pinfunction "TP_TP") (pintype "input"))
    )
    (net (code "181") (name "VDD") (class "Default")
      (node (ref "C23") (pin "1") (pinfunction "1_1") (pintype "passive"))
      (node (ref "IC8") (pin "8") (pinfunction "VDD_8") (pintype "bidirectional"))
      (node (ref "JP9") (pin "2") (pinfunction "2_2") (pintype "passive"))
      (node (ref "PTC3") (pin "P$2") (pinfunction "2_P$2") (pintype "passive"))
      (node (ref "R10") (pin "2") (pinfunction "2_2") (pintype "passive"))
      (node (ref "R9") (pin "2") (pinfunction "2_2") (pintype "passive"))
      (node (ref "U$11") (pin "1") (pinfunction "3V3_1") (pintype "power_in"))
    )
    (net (code "182") (name "unconnected-(IC8-INT-Pad7)") (class "Default")
      (node (ref "IC8") (pin "7") (pinfunction "INT_7") (pintype "bidirectional"))
    )
    (net (code "183") (name "unconnected-(K1-Pad2A)") (class "Default")
      (node (ref "K1") (pin "2A") (pinfunction "2A_2A") (pintype "bidirectional"))
    )
    (net (code "184") (name "unconnected-(K1-Pad2B)") (class "Default")
      (node (ref "K1") (pin "2B") (pinfunction "2B_2B") (pintype "bidirectional"))
    )
    (net (code "185") (name "unconnected-(K2-Pad1B)") (class "Default")
      (node (ref "K2") (pin "1B") (pinfunction "1B_1B") (pintype "bidirectional"))
    )
    (net (code "186") (name "unconnected-(K3-Pad1A)") (class "Default")
      (node (ref "K3") (pin "1A") (pinfunction "1A_1A") (pintype "bidirectional"))
    )
    (net (code "187") (name "unconnected-(K4-Pad1B)") (class "Default")
      (node (ref "K4") (pin "1B") (pinfunction "1B_1B") (pintype "bidirectional"))
    )
    (net (code "188") (name "unconnected-(K4-Pad2A)") (class "Default")
      (node (ref "K4") (pin "2A") (pinfunction "2A_2A") (pintype "bidirectional"))
    )
    (net (code "189") (name "unconnected-(TFT1-SDO-Pad7)") (class "Default")
      (node (ref "TFT1") (pin "7") (pinfunction "SDO_7") (pintype "bidirectional"))
    )
    (net (code "190") (name "unconnected-(U$2-PB2-Pad20)") (class "Default")
      (node (ref "U$2") (pin "20") (pinfunction "PB2_20") (pintype "bidirectional"))
    )
    (net (code "191") (name "unconnected-(U$2-PB7{slash}USART1_RX{slash}I2C1_SDA-Pad43)") (class "Default")
      (node (ref "U$2") (pin "43") (pinfunction "PB7/USART1_RX/I2C1_SDA_43") (pintype "bidirectional"))
    )
    (net (code "192") (name "unconnected-(U$2-PB10{slash}I2C2_SCL{slash}TIM2_CH3{slash}USART3_TX-Pad21)") (class "Default")
      (node (ref "U$2") (pin "21") (pinfunction "PB10/I2C2_SCL/TIM2_CH3/USART3_TX_21") (pintype "bidirectional"))
    )
    (net (code "193") (name "unconnected-(U$2-PB11{slash}I2C2_SDA{slash}TIM2_C4{slash}USART3_RX-Pad22)") (class "Default")
      (node (ref "U$2") (pin "22") (pinfunction "PB11/I2C2_SDA/TIM2_C4/USART3_RX_22") (pintype "bidirectional"))
    )
    (net (code "194") (name "unconnected-(U$2-PB12-Pad25)") (class "Default")
      (node (ref "U$2") (pin "25") (pinfunction "PB12_25") (pintype "bidirectional"))
    )
    (net (code "195") (name "unconnected-(U$11-GEN4{slash}GPIO23-Pad16)") (class "Default")
      (node (ref "U$11") (pin "16") (pinfunction "GEN4/GPIO23_16") (pintype "bidirectional"))
    )
    (net (code "196") (name "unconnected-(U$11-GND-Pad6)") (class "Default")
      (node (ref "U$11") (pin "6") (pinfunction "GND_6") (pintype "power_in"))
    )
    (net (code "197") (name "unconnected-(U$11-GPIO4{slash}GCKL-Pad7)") (class "Default")
      (node (ref "U$11") (pin "7") (pinfunction "GPIO4/GCKL_7") (pintype "bidirectional"))
    )
    (net (code "198") (name "unconnected-(U$11-GPIO9{slash}MISO-Pad21)") (class "Default")
      (node (ref "U$11") (pin "21") (pinfunction "GPIO9/MISO_21") (pintype "bidirectional"))
    )
    (net (code "199") (name "unconnected-(U$11-GPIO12-Pad32)") (class "Default")
      (node (ref "U$11") (pin "32") (pinfunction "GPIO12_32") (pintype "bidirectional"))
    )
    (net (code "200") (name "unconnected-(U$11-GPIO17{slash}GEN0-Pad11)") (class "Default")
      (node (ref "U$11") (pin "11") (pinfunction "GPIO17/GEN0_11") (pintype "bidirectional"))
    )
    (net (code "201") (name "unconnected-(U$11-GPIO22{slash}GEN3-Pad15)") (class "Default")
      (node (ref "U$11") (pin "15") (pinfunction "GPIO22/GEN3_15") (pintype "bidirectional"))
    )
    (net (code "202") (name "unconnected-(U$11-ID_SC-Pad28)") (class "Default")
      (node (ref "U$11") (pin "28") (pinfunction "ID_SC_28") (pintype "bidirectional"))
    )
    (net (code "203") (name "unconnected-(U$11-ID_SD-Pad27)") (class "Default")
      (node (ref "U$11") (pin "27") (pinfunction "ID_SD_27") (pintype "bidirectional"))
    )
    (net (code "204") (name "unconnected-(U$11-~{CE}{slash}GPIO7-Pad26)") (class "Default")
      (node (ref "U$11") (pin "26") (pinfunction "~{CE}/GPIO7_26") (pintype "bidirectional"))
    )
    (net (code "205") (name "unconnected-(USB-DRV-Pad22)") (class "Default")
      (node (ref "USB") (pin "22") (pinfunction "DRV_22") (pintype "bidirectional"))
    )
    (net (code "206") (name "unconnected-(USB-LED1-Pad23)") (class "Default")
      (node (ref "USB") (pin "23") (pinfunction "LED1_23") (pintype "bidirectional"))
    )
    (net (code "207") (name "unconnected-(USB-LED2-Pad24)") (class "Default")
      (node (ref "USB") (pin "24") (pinfunction "LED2_24") (pintype "bidirectional"))
    )
    (net (code "208") (name "unconnected-(USB-PWRJ-Pad25)") (class "Default")
      (node (ref "USB") (pin "25") (pinfunction "PWRJ_25") (pintype "bidirectional"))
    )
    (net (code "209") (name "unconnected-(USB-TESTJ-Pad27)") (class "Default")
      (node (ref "USB") (pin "27") (pinfunction "TESTJ_27") (pintype "bidirectional"))
    )
    (net (code "210") (name "unconnected-(X6B-S-Pad2)") (class "Default")
      (node (ref "X6") (pin "2") (pinfunction "S_2") (pintype "passive"))
    )
  )
)
